# lune-v6-rev3_2.net
KiCad netlist of a schematic drawn in EasyEDA Pro
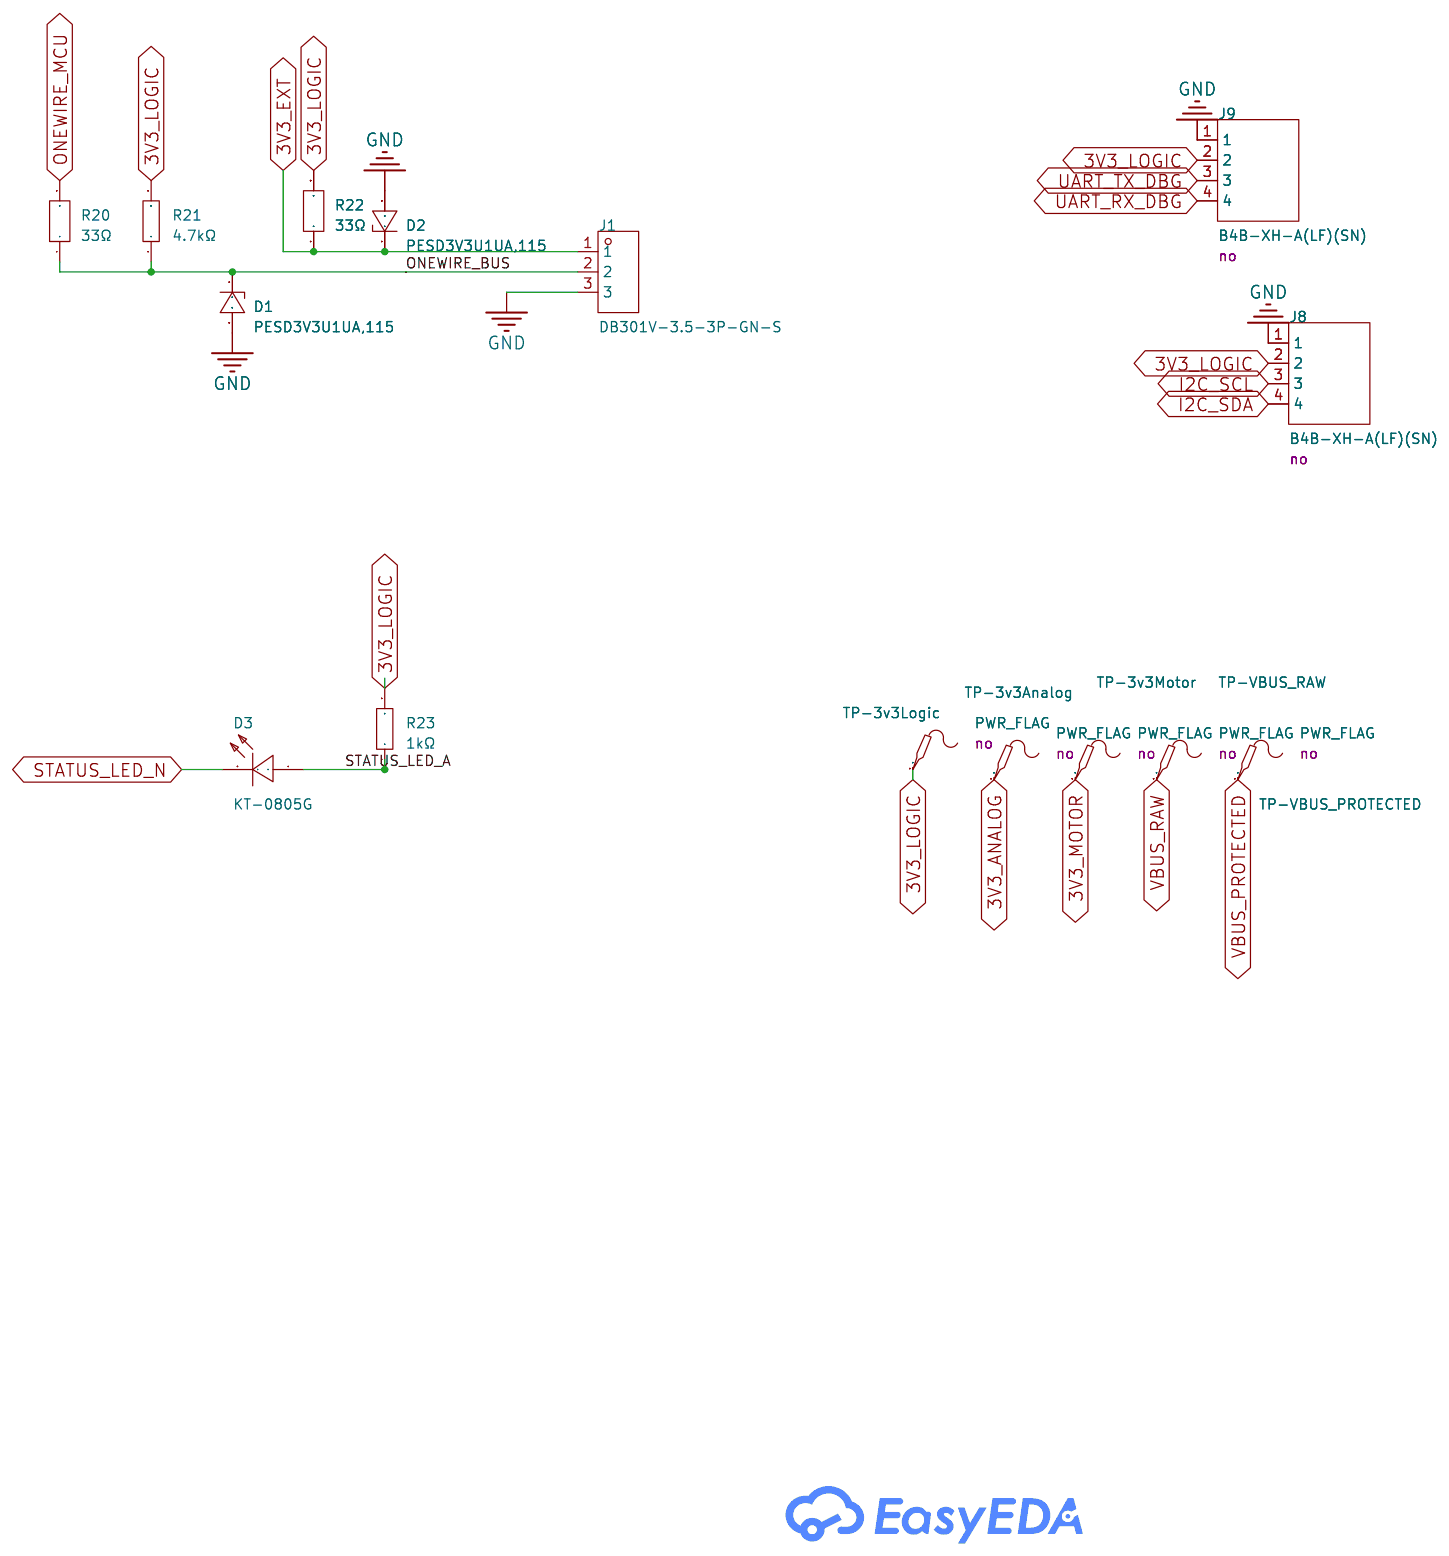
[diagram p0: Connectors]
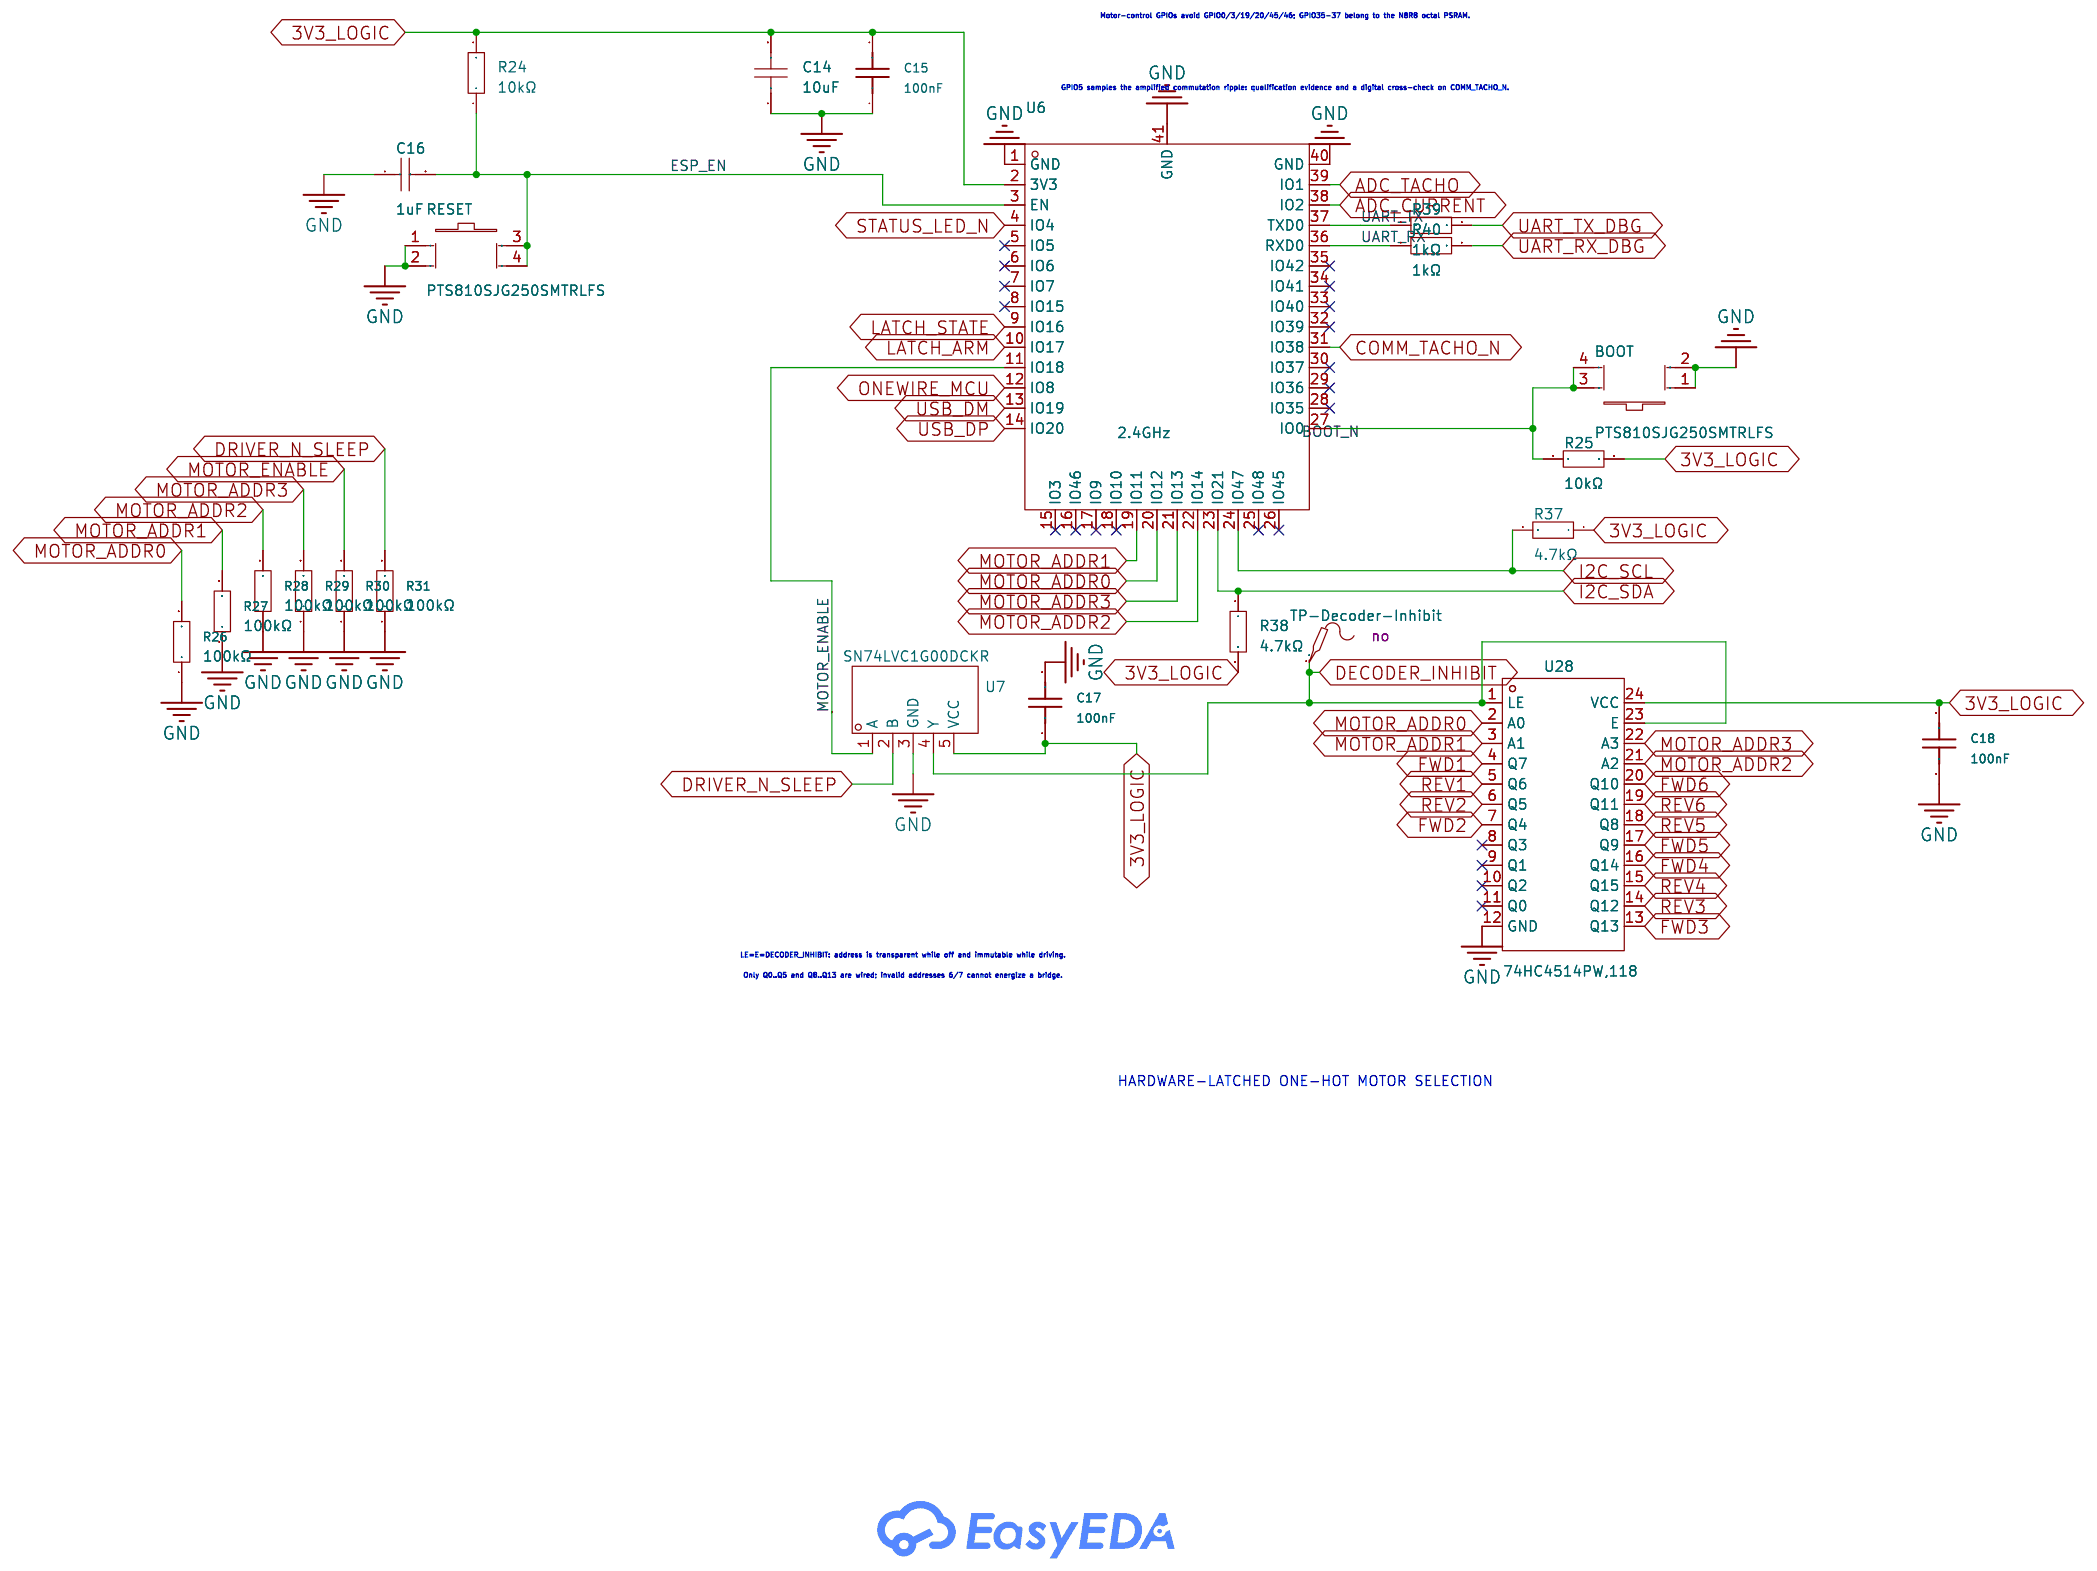
[diagram p1: Controller]
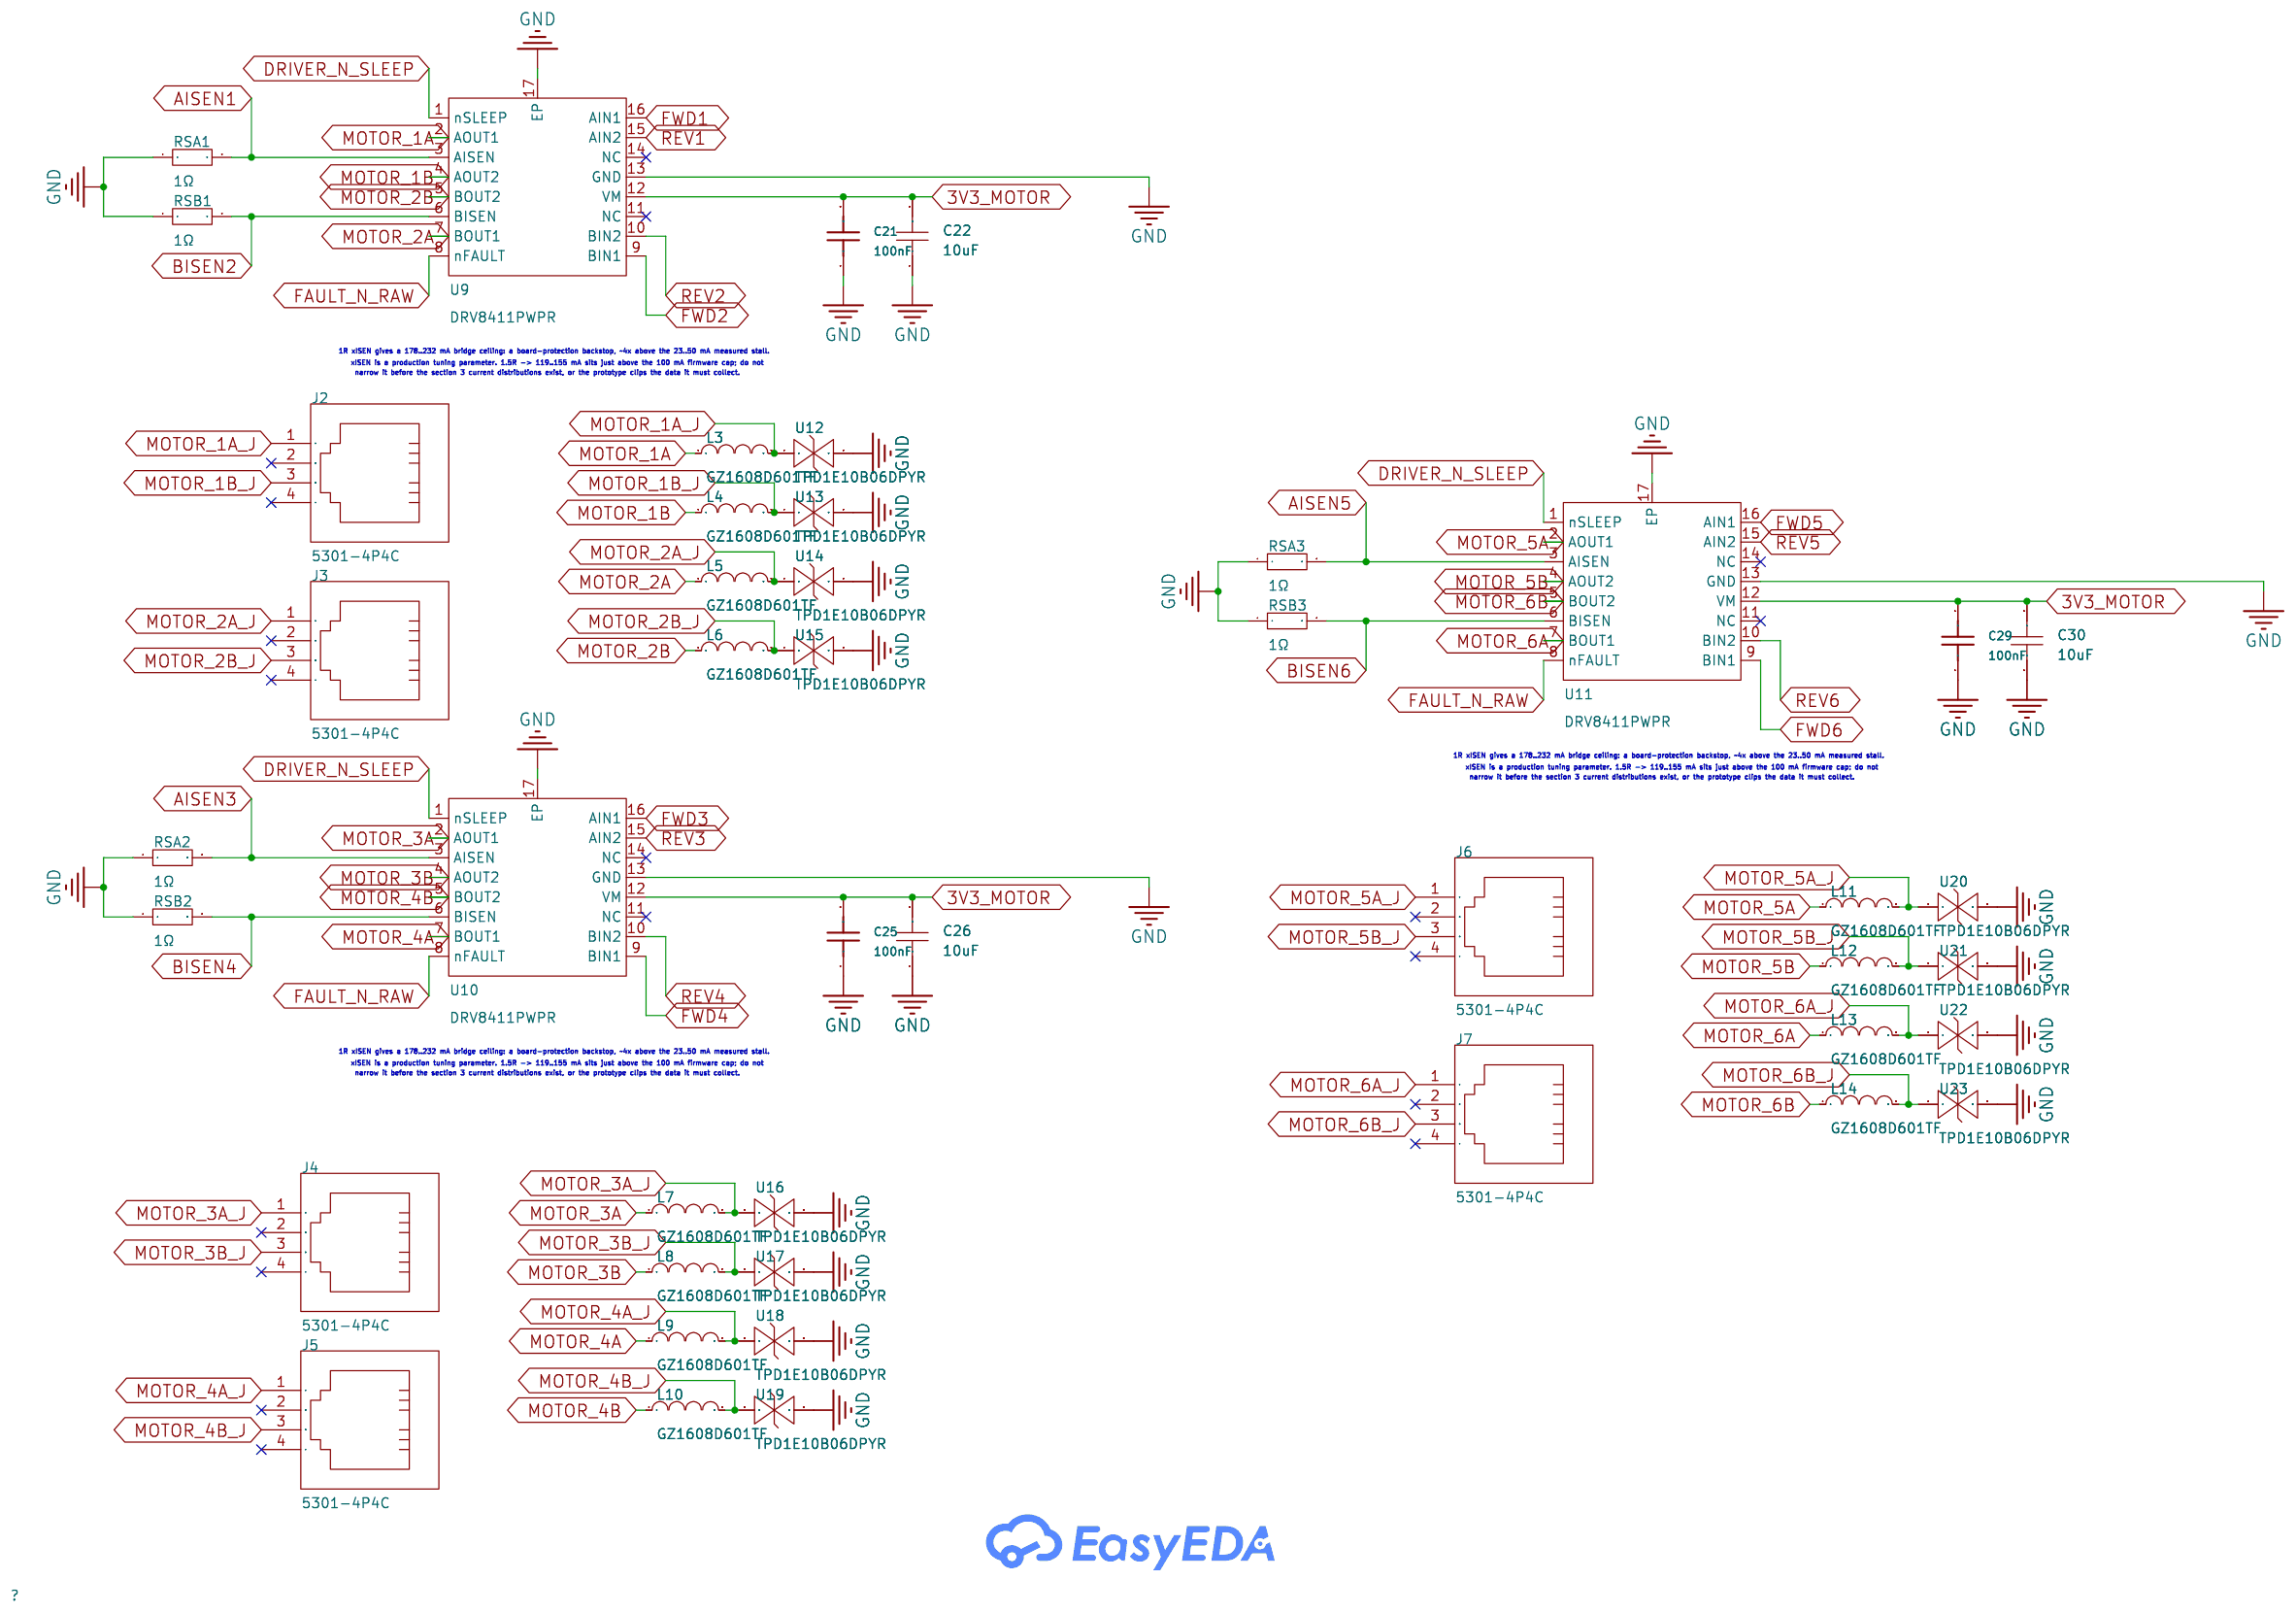
[diagram p2: Motors]
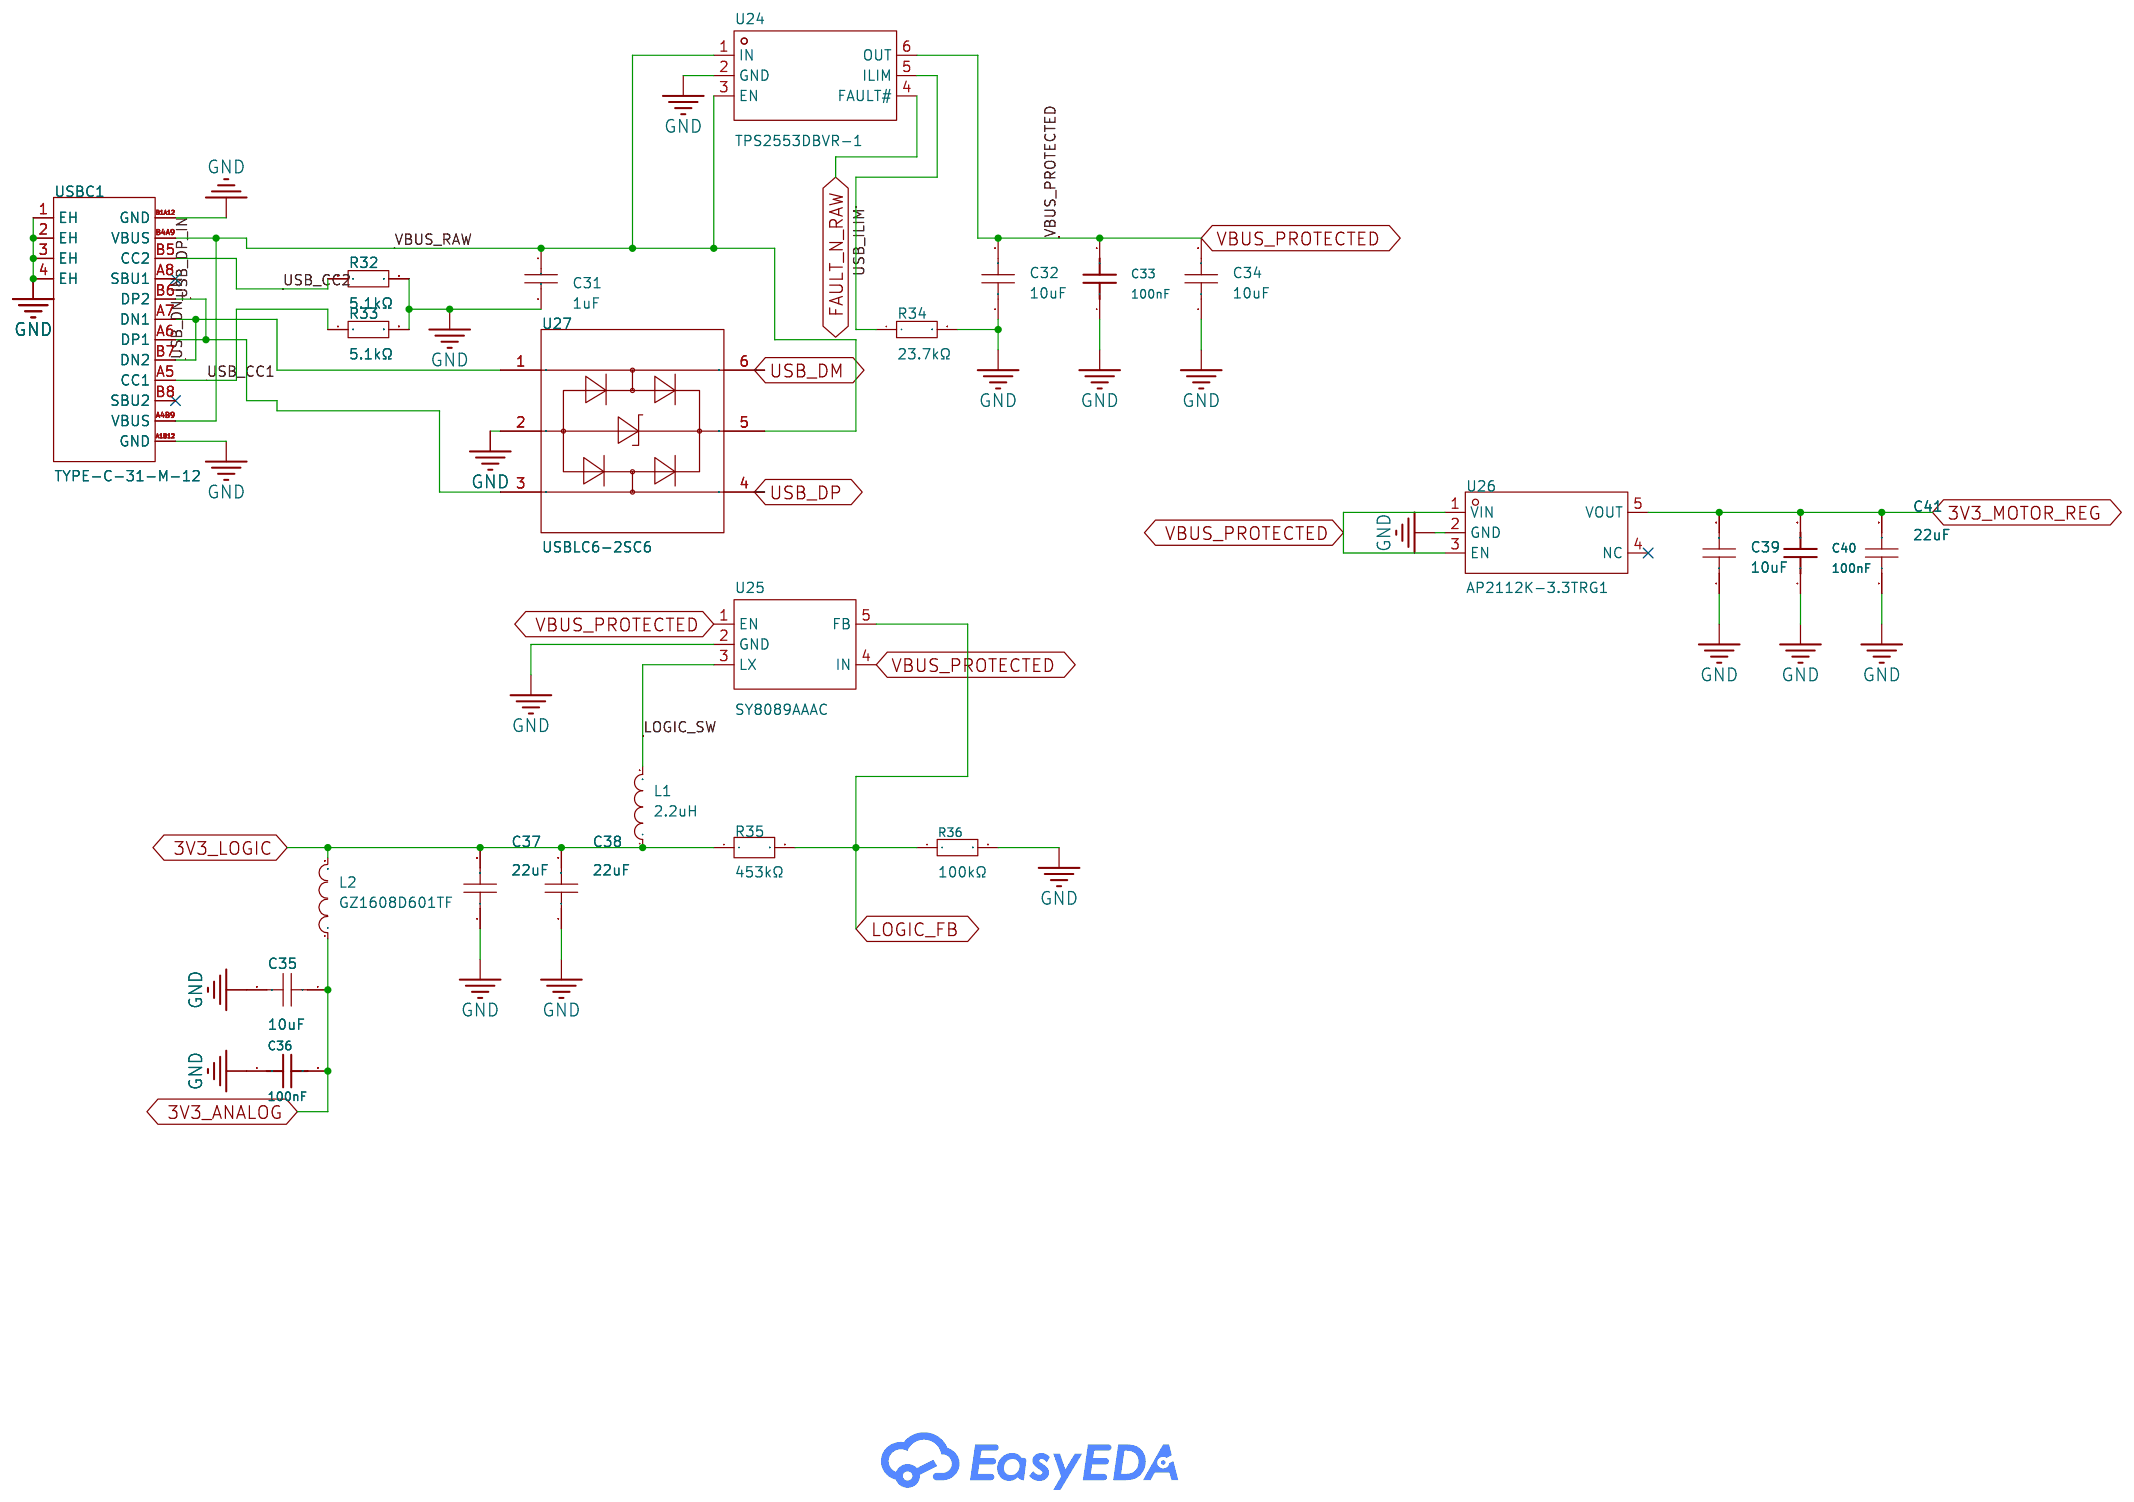
[diagram p3: Power]
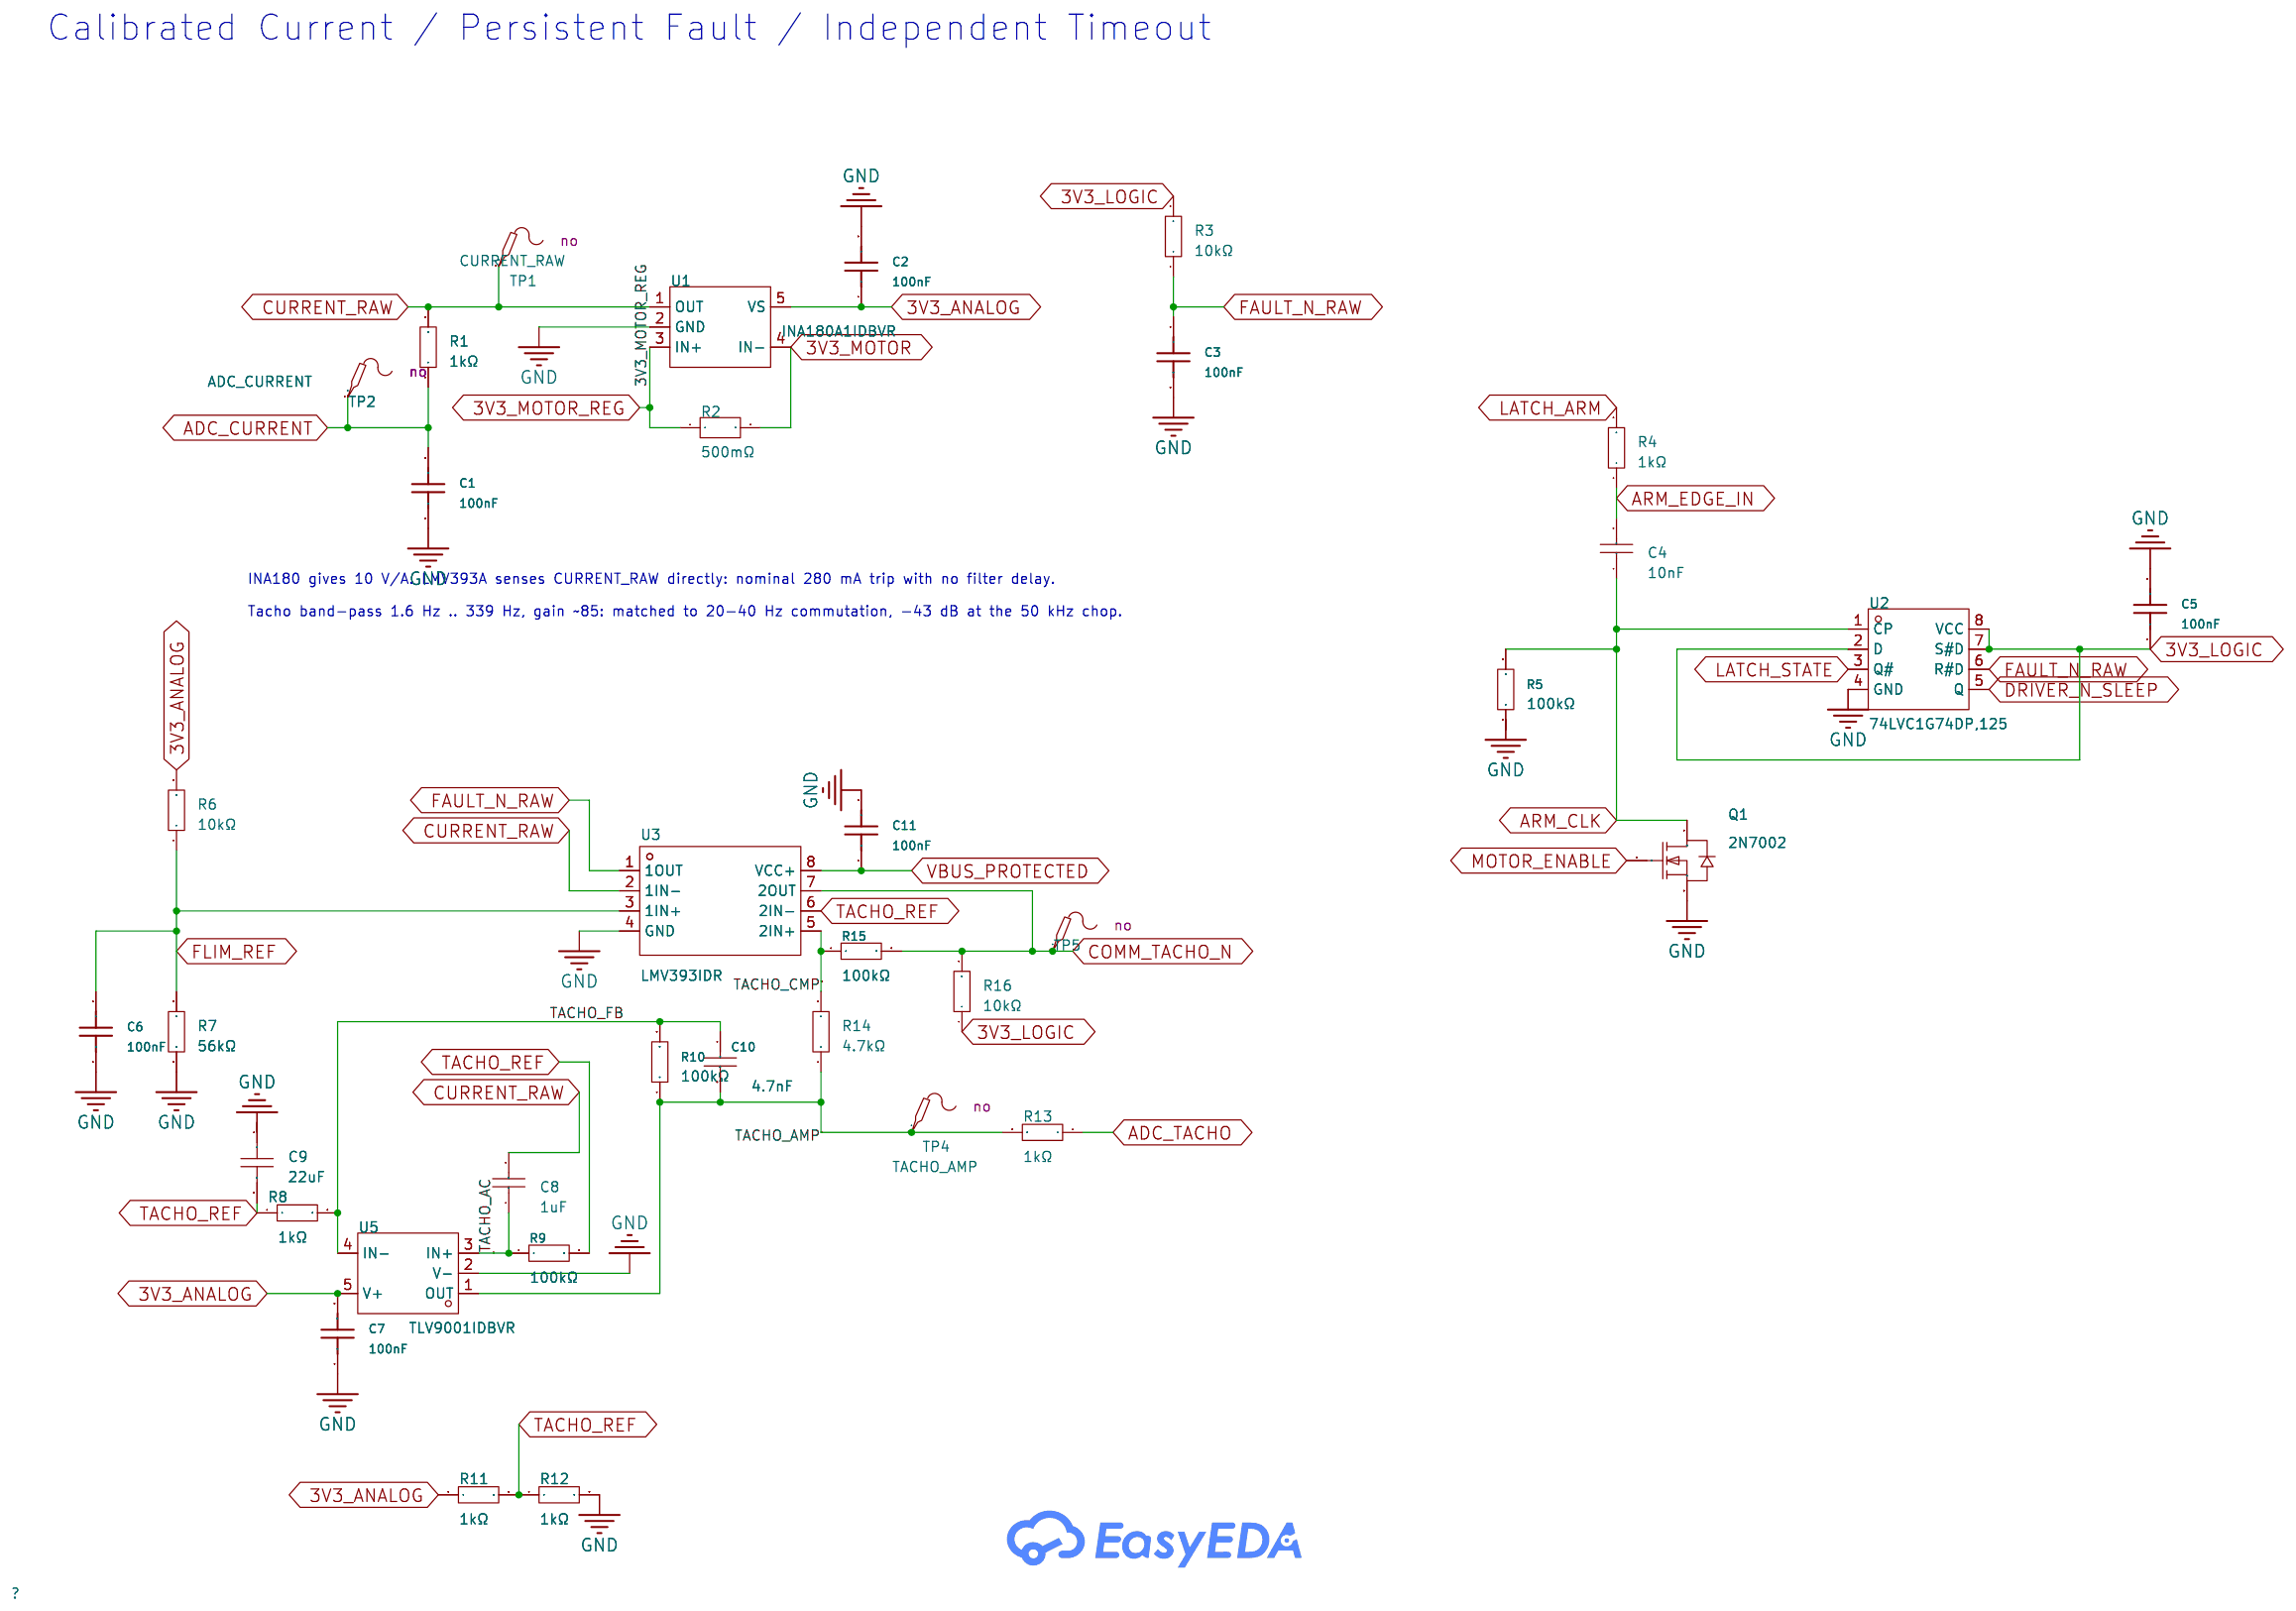
[diagram p4: Analog]

(export (version "E")
  (design (tool "Eeschema 10.0.6"))
  (components
    (comp (ref "D1")
      (value "PESD3V3U1UA,115")
      (footprint "easyedapro:SOD-323_L1.7-W1.3-LS2.5-RD")
      (fields (field (name "Manufacturer") "Nexperia(安世)"))
      (libsource (lib "easyedapro") (part "PESD3V3U1UA,115"))
    )
    (comp (ref "D2")
      (value "PESD3V3U1UA,115")
      (footprint "easyedapro:SOD-323_L1.7-W1.3-LS2.5-RD")
      (fields (field (name "Manufacturer") "Nexperia(安世)"))
      (libsource (lib "easyedapro") (part "PESD3V3U1UA,115"))
    )
    (comp (ref "D3")
      (value "KT-0805G")
      (footprint "easyedapro:LED0805-R-RD")
      (fields (field (name "Manufacturer") "KENTO"))
      (libsource (lib "easyedapro") (part "0805G (Green)"))
    )
    (comp (ref "J1")
      (value "DB301V-3.5-3P-GN-S")
      (footprint "easyedapro:CONN-TH_DB301V-3.5-3P-GN")
      (fields (field (name "Manufacturer") "DORABO(地博电气)"))
      (libsource (lib "easyedapro") (part "DB301V-3.5-3P-GN"))
    )
    (comp (ref "J8")
      (value "B4B-XH-A(LF)(SN)")
      (footprint "easyedapro:CONN-TH_B4B-XH-A-LF-SN")
      (fields (field (name "Manufacturer") "JST") (field (name "Add into BOM") "no"))
      (libsource (lib "easyedapro") (part "B4B-XH-A(LF)(SN)"))
    )
    (comp (ref "J9")
      (value "B4B-XH-A(LF)(SN)")
      (footprint "easyedapro:CONN-TH_B4B-XH-A-LF-SN")
      (fields (field (name "Manufacturer") "JST") (field (name "Add into BOM") "no"))
      (libsource (lib "easyedapro") (part "B4B-XH-A(LF)(SN)"))
    )
    (comp (ref "R20")
      (value "33Ω")
      (footprint "easyedapro:R0603")
      (fields
        (field (name "Manufacturer Part") "CRCW060333R0FKEA")
        (field (name "Manufacturer") "VISHAY(威世)")
      )
      (libsource (lib "easyedapro") (part "CRCW060333R0FKEA"))
    )
    (comp (ref "R21")
      (value "4.7kΩ")
      (footprint "easyedapro:R0603")
      (fields (field (name "Manufacturer Part") "RC0603FR-074K7L") (field (name "Manufacturer") "YAGEO(国巨)"))
      (libsource (lib "easyedapro") (part "RC0603FR-074K7L"))
    )
    (comp (ref "R22")
      (value "33Ω")
      (footprint "easyedapro:R0603")
      (fields
        (field (name "Manufacturer Part") "CRCW060333R0FKEA")
        (field (name "Manufacturer") "VISHAY(威世)")
      )
      (libsource (lib "easyedapro") (part "CRCW060333R0FKEA"))
    )
    (comp (ref "R23")
      (value "1kΩ")
      (footprint "easyedapro:R0603")
      (fields (field (name "Manufacturer Part") "RC0603FR-071KL") (field (name "Manufacturer") "YAGEO(国巨)"))
      (libsource (lib "easyedapro") (part "RC0603FR-071KL"))
    )
    (comp (ref "TP-3v3Analog")
      (value "PWR_FLAG")
      (footprint "easyedapro:Test-Point-0.5mm")
      (description "Test Point 测试点")
      (fields (field (name "Add into BOM") "no"))
      (libsource (lib "easyedapro") (part "Test-Point"))
    )
    (comp (ref "TP-3v3Logic")
      (value "PWR_FLAG")
      (footprint "easyedapro:Test-Point-0.5mm")
      (description "Test Point 测试点")
      (fields (field (name "Add into BOM") "no"))
      (libsource (lib "easyedapro") (part "Test-Point"))
    )
    (comp (ref "TP-3v3Motor")
      (value "PWR_FLAG")
      (footprint "easyedapro:Test-Point-0.5mm")
      (description "Test Point 测试点")
      (fields (field (name "Add into BOM") "no"))
      (libsource (lib "easyedapro") (part "Test-Point"))
    )
    (comp (ref "TP-VBUS_PROTECTED")
      (value "PWR_FLAG")
      (footprint "easyedapro:Test-Point-0.5mm")
      (description "Test Point 测试点")
      (fields (field (name "Add into BOM") "no"))
      (libsource (lib "easyedapro") (part "Test-Point"))
    )
    (comp (ref "TP-VBUS_RAW")
      (value "PWR_FLAG")
      (footprint "easyedapro:Test-Point-0.5mm")
      (description "Test Point 测试点")
      (fields (field (name "Add into BOM") "no"))
      (libsource (lib "easyedapro") (part "Test-Point"))
    )
    (comp (ref "BOOT")
      (value "PTS810SJG250SMTRLFS")
      (footprint "easyedapro:SW-SMD_4P_PTS810SJM250SMTRLFS")
      (fields (field (name "Manufacturer") "C&K"))
      (libsource (lib "easyedapro") (part "PTS810SJG250SMTRLFS"))
    )
    (comp (ref "C14")
      (value "10uF")
      (footprint "easyedapro:C0603")
      (description "Capacitance:10uF Tolerance:±10% Tolerance:±10% Voltage Rating:16V Temperature Coefficient:X5R")
      (fields
        (field (name "Manufacturer Part") "TCC0603X5R106K160CT")
        (field (name "Manufacturer") "CCTC(三环)")
      )
      (libsource (lib "easyedapro") (part "TCC0603X5R106K160CT"))
    )
    (comp (ref "C15")
      (value "100nF")
      (footprint "easyedapro:C0603")
      (description "Capacitance:100nF Tolerance:±10% Tolerance:±10% Voltage Rating:50V Temperature Coefficient:X7R")
      (fields
        (field (name "Manufacturer Part") "CC0603KRX7R9BB104")
        (field (name "Manufacturer") "YAGEO(国巨)")
      )
      (libsource (lib "easyedapro") (part "CC0603KRX7R9BB104"))
    )
    (comp (ref "C16")
      (value "1uF")
      (footprint "easyedapro:C0603")
      (description "Capacitance:1uF Tolerance:±10% Tolerance:±10% Voltage Rating:16V Temperature Coefficient:X7R")
      (fields (field (name "Manufacturer Part") "0603B105K160CT") (field (name "Manufacturer") "Walsin(华新科)"))
      (libsource (lib "easyedapro") (part "0603B105K160"))
    )
    (comp (ref "C17")
      (value "100nF")
      (footprint "easyedapro:C0603")
      (description "Capacitance:100nF Tolerance:±10% Tolerance:±10% Voltage Rating:50V Temperature Coefficient:X7R")
      (fields
        (field (name "Manufacturer Part") "CC0603KRX7R9BB104")
        (field (name "Manufacturer") "YAGEO(国巨)")
      )
      (libsource (lib "easyedapro") (part "CC0603KRX7R9BB104"))
    )
    (comp (ref "C18")
      (value "100nF")
      (footprint "easyedapro:C0603")
      (description "Capacitance:100nF Tolerance:±10% Tolerance:±10% Voltage Rating:50V Temperature Coefficient:X7R")
      (fields
        (field (name "Manufacturer Part") "CC0603KRX7R9BB104")
        (field (name "Manufacturer") "YAGEO(国巨)")
      )
      (libsource (lib "easyedapro") (part "CC0603KRX7R9BB104"))
    )
    (comp (ref "R24")
      (value "10kΩ")
      (footprint "easyedapro:R0603")
      (fields (field (name "Manufacturer Part") "RC0603FR-0710KL") (field (name "Manufacturer") "YAGEO(国巨)"))
      (libsource (lib "easyedapro") (part "RC0603FR-0710KL"))
    )
    (comp (ref "R25")
      (value "10kΩ")
      (footprint "easyedapro:R0603")
      (fields (field (name "Manufacturer Part") "RC0603FR-0710KL") (field (name "Manufacturer") "YAGEO(国巨)"))
      (libsource (lib "easyedapro") (part "RC0603FR-0710KL"))
    )
    (comp (ref "R26")
      (value "100kΩ")
      (footprint "easyedapro:R0603")
      (fields (field (name "Manufacturer Part") "RC0603FR-07100KL") (field (name "Manufacturer") "YAGEO(国巨)"))
      (libsource (lib "easyedapro") (part "RC0603FR-07100KL"))
    )
    (comp (ref "R27")
      (value "100kΩ")
      (footprint "easyedapro:R0603")
      (fields (field (name "Manufacturer Part") "RC0603FR-07100KL") (field (name "Manufacturer") "YAGEO(国巨)"))
      (libsource (lib "easyedapro") (part "RC0603FR-07100KL"))
    )
    (comp (ref "R28")
      (value "100kΩ")
      (footprint "easyedapro:R0603")
      (fields (field (name "Manufacturer Part") "RC0603FR-07100KL") (field (name "Manufacturer") "YAGEO(国巨)"))
      (libsource (lib "easyedapro") (part "RC0603FR-07100KL"))
    )
    (comp (ref "R29")
      (value "100kΩ")
      (footprint "easyedapro:R0603")
      (fields (field (name "Manufacturer Part") "RC0603FR-07100KL") (field (name "Manufacturer") "YAGEO(国巨)"))
      (libsource (lib "easyedapro") (part "RC0603FR-07100KL"))
    )
    (comp (ref "R30")
      (value "100kΩ")
      (footprint "easyedapro:R0603")
      (fields (field (name "Manufacturer Part") "RC0603FR-07100KL") (field (name "Manufacturer") "YAGEO(国巨)"))
      (libsource (lib "easyedapro") (part "RC0603FR-07100KL"))
    )
    (comp (ref "R31")
      (value "100kΩ")
      (footprint "easyedapro:R0603")
      (fields (field (name "Manufacturer Part") "RC0603FR-07100KL") (field (name "Manufacturer") "YAGEO(国巨)"))
      (libsource (lib "easyedapro") (part "RC0603FR-07100KL"))
    )
    (comp (ref "R37")
      (value "4.7kΩ")
      (footprint "easyedapro:R0603")
      (fields (field (name "Manufacturer Part") "RC0603FR-074K7L") (field (name "Manufacturer") "YAGEO(国巨)"))
      (libsource (lib "easyedapro") (part "RC0603FR-074K7L"))
    )
    (comp (ref "R38")
      (value "4.7kΩ")
      (footprint "easyedapro:R0603")
      (fields (field (name "Manufacturer Part") "RC0603FR-074K7L") (field (name "Manufacturer") "YAGEO(国巨)"))
      (libsource (lib "easyedapro") (part "RC0603FR-074K7L"))
    )
    (comp (ref "R39")
      (value "1kΩ")
      (footprint "easyedapro:R0603")
      (fields (field (name "Manufacturer Part") "RC0603FR-071KL") (field (name "Manufacturer") "YAGEO(国巨)"))
      (libsource (lib "easyedapro") (part "RC0603FR-071KL"))
    )
    (comp (ref "R40")
      (value "1kΩ")
      (footprint "easyedapro:R0603")
      (fields (field (name "Manufacturer Part") "RC0603FR-071KL") (field (name "Manufacturer") "YAGEO(国巨)"))
      (libsource (lib "easyedapro") (part "RC0603FR-071KL"))
    )
    (comp (ref "RESET")
      (value "PTS810SJG250SMTRLFS")
      (footprint "easyedapro:SW-SMD_4P_PTS810SJM250SMTRLFS")
      (fields (field (name "Manufacturer") "C&K"))
      (libsource (lib "easyedapro") (part "PTS810SJG250SMTRLFS"))
    )
    (comp (ref "TP-Decoder-Inhibit")
      (value "~")
      (footprint "easyedapro:Test-Point-0.5mm")
      (description "Test Point 测试点")
      (fields (field (name "Add into BOM") "no"))
      (libsource (lib "easyedapro") (part "Test-Point"))
    )
    (comp (ref "U6")
      (value "2.4GHz")
      (footprint "easyedapro:WIRELM-SMD_ESP32-S3-WROOM-1")
      (fields
        (field (name "Manufacturer Part") "ESP32-S3-WROOM-1-N8R8")
        (field (name "Manufacturer") "ESPRESSIF(乐鑫)")
      )
      (libsource (lib "easyedapro") (part "ESP32-S3-WROOM-1(N8R8)"))
    )
    (comp (ref "U7")
      (value "SN74LVC1G00DCKR")
      (footprint "easyedapro:SOT-353_L2.1-W1.3-P0.65-LS2.3-BR")
      (fields (field (name "Manufacturer") "TI(德州仪器)"))
      (libsource (lib "easyedapro") (part "SN74LVC1G00DCKR"))
    )
    (comp (ref "U28")
      (value "74HC4514PW,118")
      (footprint "easyedapro:TSSOP-24_L7.8-W4.4-P0.65-LS6.4-BL")
      (fields (field (name "Manufacturer") "Nexperia(安世)"))
      (libsource (lib "easyedapro") (part "74HC4514PW,118"))
    )
    (comp (ref "C21")
      (value "100nF")
      (footprint "easyedapro:C0603")
      (description "Capacitance:100nF Tolerance:±10% Tolerance:±10% Voltage Rating:50V Temperature Coefficient:X7R")
      (fields
        (field (name "Manufacturer Part") "CC0603KRX7R9BB104")
        (field (name "Manufacturer") "YAGEO(国巨)")
      )
      (libsource (lib "easyedapro") (part "CC0603KRX7R9BB104"))
    )
    (comp (ref "C22")
      (value "10uF")
      (footprint "easyedapro:C0603")
      (description "Capacitance:10uF Tolerance:±10% Tolerance:±10% Voltage Rating:16V Temperature Coefficient:X5R")
      (fields
        (field (name "Manufacturer Part") "TCC0603X5R106K160CT")
        (field (name "Manufacturer") "CCTC(三环)")
      )
      (libsource (lib "easyedapro") (part "TCC0603X5R106K160CT"))
    )
    (comp (ref "C25")
      (value "100nF")
      (footprint "easyedapro:C0603")
      (description "Capacitance:100nF Tolerance:±10% Tolerance:±10% Voltage Rating:50V Temperature Coefficient:X7R")
      (fields
        (field (name "Manufacturer Part") "CC0603KRX7R9BB104")
        (field (name "Manufacturer") "YAGEO(国巨)")
      )
      (libsource (lib "easyedapro") (part "CC0603KRX7R9BB104"))
    )
    (comp (ref "C26")
      (value "10uF")
      (footprint "easyedapro:C0603")
      (description "Capacitance:10uF Tolerance:±10% Tolerance:±10% Voltage Rating:16V Temperature Coefficient:X5R")
      (fields
        (field (name "Manufacturer Part") "TCC0603X5R106K160CT")
        (field (name "Manufacturer") "CCTC(三环)")
      )
      (libsource (lib "easyedapro") (part "TCC0603X5R106K160CT"))
    )
    (comp (ref "C29")
      (value "100nF")
      (footprint "easyedapro:C0603")
      (description "Capacitance:100nF Tolerance:±10% Tolerance:±10% Voltage Rating:50V Temperature Coefficient:X7R")
      (fields
        (field (name "Manufacturer Part") "CC0603KRX7R9BB104")
        (field (name "Manufacturer") "YAGEO(国巨)")
      )
      (libsource (lib "easyedapro") (part "CC0603KRX7R9BB104"))
    )
    (comp (ref "C30")
      (value "10uF")
      (footprint "easyedapro:C0603")
      (description "Capacitance:10uF Tolerance:±10% Tolerance:±10% Voltage Rating:16V Temperature Coefficient:X5R")
      (fields
        (field (name "Manufacturer Part") "TCC0603X5R106K160CT")
        (field (name "Manufacturer") "CCTC(三环)")
      )
      (libsource (lib "easyedapro") (part "TCC0603X5R106K160CT"))
    )
    (comp (ref "J2")
      (value "5301-4P4C")
      (footprint "easyedapro:RJ11-TH_RJ11-4P4C")
      (fields (field (name "Manufacturer") "EVERCOM(恒连)"))
      (libsource (lib "easyedapro") (part "5301-4P4C"))
    )
    (comp (ref "J3")
      (value "5301-4P4C")
      (footprint "easyedapro:RJ11-TH_RJ11-4P4C")
      (fields (field (name "Manufacturer") "EVERCOM(恒连)"))
      (libsource (lib "easyedapro") (part "5301-4P4C"))
    )
    (comp (ref "J4")
      (value "5301-4P4C")
      (footprint "easyedapro:RJ11-TH_RJ11-4P4C")
      (fields (field (name "Manufacturer") "EVERCOM(恒连)"))
      (libsource (lib "easyedapro") (part "5301-4P4C"))
    )
    (comp (ref "J5")
      (value "5301-4P4C")
      (footprint "easyedapro:RJ11-TH_RJ11-4P4C")
      (fields (field (name "Manufacturer") "EVERCOM(恒连)"))
      (libsource (lib "easyedapro") (part "5301-4P4C"))
    )
    (comp (ref "J6")
      (value "5301-4P4C")
      (footprint "easyedapro:RJ11-TH_RJ11-4P4C")
      (fields (field (name "Manufacturer") "EVERCOM(恒连)"))
      (libsource (lib "easyedapro") (part "5301-4P4C"))
    )
    (comp (ref "J7")
      (value "5301-4P4C")
      (footprint "easyedapro:RJ11-TH_RJ11-4P4C")
      (fields (field (name "Manufacturer") "EVERCOM(恒连)"))
      (libsource (lib "easyedapro") (part "5301-4P4C"))
    )
    (comp (ref "L3")
      (value "GZ1608D601TF")
      (footprint "easyedapro:L0603")
      (fields (field (name "Manufacturer") "Sunlord(顺络)"))
      (libsource (lib "easyedapro") (part "GZ1608D601TF"))
    )
    (comp (ref "L4")
      (value "GZ1608D601TF")
      (footprint "easyedapro:L0603")
      (fields (field (name "Manufacturer") "Sunlord(顺络)"))
      (libsource (lib "easyedapro") (part "GZ1608D601TF"))
    )
    (comp (ref "L5")
      (value "GZ1608D601TF")
      (footprint "easyedapro:L0603")
      (fields (field (name "Manufacturer") "Sunlord(顺络)"))
      (libsource (lib "easyedapro") (part "GZ1608D601TF"))
    )
    (comp (ref "L6")
      (value "GZ1608D601TF")
      (footprint "easyedapro:L0603")
      (fields (field (name "Manufacturer") "Sunlord(顺络)"))
      (libsource (lib "easyedapro") (part "GZ1608D601TF"))
    )
    (comp (ref "L7")
      (value "GZ1608D601TF")
      (footprint "easyedapro:L0603")
      (fields (field (name "Manufacturer") "Sunlord(顺络)"))
      (libsource (lib "easyedapro") (part "GZ1608D601TF"))
    )
    (comp (ref "L8")
      (value "GZ1608D601TF")
      (footprint "easyedapro:L0603")
      (fields (field (name "Manufacturer") "Sunlord(顺络)"))
      (libsource (lib "easyedapro") (part "GZ1608D601TF"))
    )
    (comp (ref "L9")
      (value "GZ1608D601TF")
      (footprint "easyedapro:L0603")
      (fields (field (name "Manufacturer") "Sunlord(顺络)"))
      (libsource (lib "easyedapro") (part "GZ1608D601TF"))
    )
    (comp (ref "L10")
      (value "GZ1608D601TF")
      (footprint "easyedapro:L0603")
      (fields (field (name "Manufacturer") "Sunlord(顺络)"))
      (libsource (lib "easyedapro") (part "GZ1608D601TF"))
    )
    (comp (ref "L11")
      (value "GZ1608D601TF")
      (footprint "easyedapro:L0603")
      (fields (field (name "Manufacturer") "Sunlord(顺络)"))
      (libsource (lib "easyedapro") (part "GZ1608D601TF"))
    )
    (comp (ref "L12")
      (value "GZ1608D601TF")
      (footprint "easyedapro:L0603")
      (fields (field (name "Manufacturer") "Sunlord(顺络)"))
      (libsource (lib "easyedapro") (part "GZ1608D601TF"))
    )
    (comp (ref "L13")
      (value "GZ1608D601TF")
      (footprint "easyedapro:L0603")
      (fields (field (name "Manufacturer") "Sunlord(顺络)"))
      (libsource (lib "easyedapro") (part "GZ1608D601TF"))
    )
    (comp (ref "L14")
      (value "GZ1608D601TF")
      (footprint "easyedapro:L0603")
      (fields (field (name "Manufacturer") "Sunlord(顺络)"))
      (libsource (lib "easyedapro") (part "GZ1608D601TF"))
    )
    (comp (ref "RSA1")
      (value "1Ω")
      (footprint "easyedapro:R0603")
      (fields (field (name "Manufacturer Part") "RC0603FR-071RL") (field (name "Manufacturer") "YAGEO(国巨)"))
      (libsource (lib "easyedapro") (part "RC0603FR-071RL"))
    )
    (comp (ref "RSA2")
      (value "1Ω")
      (footprint "easyedapro:R0603")
      (fields (field (name "Manufacturer Part") "RC0603FR-071RL") (field (name "Manufacturer") "YAGEO(国巨)"))
      (libsource (lib "easyedapro") (part "RC0603FR-071RL"))
    )
    (comp (ref "RSA3")
      (value "1Ω")
      (footprint "easyedapro:R0603")
      (fields (field (name "Manufacturer Part") "RC0603FR-071RL") (field (name "Manufacturer") "YAGEO(国巨)"))
      (libsource (lib "easyedapro") (part "RC0603FR-071RL"))
    )
    (comp (ref "RSB1")
      (value "1Ω")
      (footprint "easyedapro:R0603")
      (fields (field (name "Manufacturer Part") "RC0603FR-071RL") (field (name "Manufacturer") "YAGEO(国巨)"))
      (libsource (lib "easyedapro") (part "RC0603FR-071RL"))
    )
    (comp (ref "RSB2")
      (value "1Ω")
      (footprint "easyedapro:R0603")
      (fields (field (name "Manufacturer Part") "RC0603FR-071RL") (field (name "Manufacturer") "YAGEO(国巨)"))
      (libsource (lib "easyedapro") (part "RC0603FR-071RL"))
    )
    (comp (ref "RSB3")
      (value "1Ω")
      (footprint "easyedapro:R0603")
      (fields (field (name "Manufacturer Part") "RC0603FR-071RL") (field (name "Manufacturer") "YAGEO(国巨)"))
      (libsource (lib "easyedapro") (part "RC0603FR-071RL"))
    )
    (comp (ref "U9")
      (value "DRV8411PWPR")
      (footprint "easyedapro:HTSSOP-16_L5.0-W4.4-P0.65-LS6.4-TL-EP-1")
      (fields (field (name "Manufacturer") "TI(德州仪器)"))
      (libsource (lib "easyedapro") (part "DRV8411PWPR"))
    )
    (comp (ref "U10")
      (value "DRV8411PWPR")
      (footprint "easyedapro:HTSSOP-16_L5.0-W4.4-P0.65-LS6.4-TL-EP-1")
      (fields (field (name "Manufacturer") "TI(德州仪器)"))
      (libsource (lib "easyedapro") (part "DRV8411PWPR"))
    )
    (comp (ref "U11")
      (value "DRV8411PWPR")
      (footprint "easyedapro:HTSSOP-16_L5.0-W4.4-P0.65-LS6.4-TL-EP-1")
      (fields (field (name "Manufacturer") "TI(德州仪器)"))
      (libsource (lib "easyedapro") (part "DRV8411PWPR"))
    )
    (comp (ref "U12")
      (value "TPD1E10B06DPYR")
      (footprint "easyedapro:X1SON-2_L1.0-W0.6-P0.65-BI-1")
      (fields (field (name "Manufacturer") "TI(德州仪器)"))
      (libsource (lib "easyedapro") (part "TPD1E10B06DPYR"))
    )
    (comp (ref "U13")
      (value "TPD1E10B06DPYR")
      (footprint "easyedapro:X1SON-2_L1.0-W0.6-P0.65-BI-1")
      (fields (field (name "Manufacturer") "TI(德州仪器)"))
      (libsource (lib "easyedapro") (part "TPD1E10B06DPYR"))
    )
    (comp (ref "U14")
      (value "TPD1E10B06DPYR")
      (footprint "easyedapro:X1SON-2_L1.0-W0.6-P0.65-BI-1")
      (fields (field (name "Manufacturer") "TI(德州仪器)"))
      (libsource (lib "easyedapro") (part "TPD1E10B06DPYR"))
    )
    (comp (ref "U15")
      (value "TPD1E10B06DPYR")
      (footprint "easyedapro:X1SON-2_L1.0-W0.6-P0.65-BI-1")
      (fields (field (name "Manufacturer") "TI(德州仪器)"))
      (libsource (lib "easyedapro") (part "TPD1E10B06DPYR"))
    )
    (comp (ref "U16")
      (value "TPD1E10B06DPYR")
      (footprint "easyedapro:X1SON-2_L1.0-W0.6-P0.65-BI-1")
      (fields (field (name "Manufacturer") "TI(德州仪器)"))
      (libsource (lib "easyedapro") (part "TPD1E10B06DPYR"))
    )
    (comp (ref "U17")
      (value "TPD1E10B06DPYR")
      (footprint "easyedapro:X1SON-2_L1.0-W0.6-P0.65-BI-1")
      (fields (field (name "Manufacturer") "TI(德州仪器)"))
      (libsource (lib "easyedapro") (part "TPD1E10B06DPYR"))
    )
    (comp (ref "U18")
      (value "TPD1E10B06DPYR")
      (footprint "easyedapro:X1SON-2_L1.0-W0.6-P0.65-BI-1")
      (fields (field (name "Manufacturer") "TI(德州仪器)"))
      (libsource (lib "easyedapro") (part "TPD1E10B06DPYR"))
    )
    (comp (ref "U19")
      (value "TPD1E10B06DPYR")
      (footprint "easyedapro:X1SON-2_L1.0-W0.6-P0.65-BI-1")
      (fields (field (name "Manufacturer") "TI(德州仪器)"))
      (libsource (lib "easyedapro") (part "TPD1E10B06DPYR"))
    )
    (comp (ref "U20")
      (value "TPD1E10B06DPYR")
      (footprint "easyedapro:X1SON-2_L1.0-W0.6-P0.65-BI-1")
      (fields (field (name "Manufacturer") "TI(德州仪器)"))
      (libsource (lib "easyedapro") (part "TPD1E10B06DPYR"))
    )
    (comp (ref "U21")
      (value "TPD1E10B06DPYR")
      (footprint "easyedapro:X1SON-2_L1.0-W0.6-P0.65-BI-1")
      (fields (field (name "Manufacturer") "TI(德州仪器)"))
      (libsource (lib "easyedapro") (part "TPD1E10B06DPYR"))
    )
    (comp (ref "U22")
      (value "TPD1E10B06DPYR")
      (footprint "easyedapro:X1SON-2_L1.0-W0.6-P0.65-BI-1")
      (fields (field (name "Manufacturer") "TI(德州仪器)"))
      (libsource (lib "easyedapro") (part "TPD1E10B06DPYR"))
    )
    (comp (ref "U23")
      (value "TPD1E10B06DPYR")
      (footprint "easyedapro:X1SON-2_L1.0-W0.6-P0.65-BI-1")
      (fields (field (name "Manufacturer") "TI(德州仪器)"))
      (libsource (lib "easyedapro") (part "TPD1E10B06DPYR"))
    )
    (comp (ref "C31")
      (value "1uF")
      (footprint "easyedapro:C0603")
      (description "Capacitance:1uF Tolerance:±10% Tolerance:±10% Voltage Rating:16V Temperature Coefficient:X7R")
      (fields (field (name "Manufacturer Part") "0603B105K160CT") (field (name "Manufacturer") "Walsin(华新科)"))
      (libsource (lib "easyedapro") (part "0603B105K160"))
    )
    (comp (ref "C32")
      (value "10uF")
      (footprint "easyedapro:C0603")
      (description "Capacitance:10uF Tolerance:±10% Tolerance:±10% Voltage Rating:16V Temperature Coefficient:X5R")
      (fields
        (field (name "Manufacturer Part") "TCC0603X5R106K160CT")
        (field (name "Manufacturer") "CCTC(三环)")
      )
      (libsource (lib "easyedapro") (part "TCC0603X5R106K160CT"))
    )
    (comp (ref "C33")
      (value "100nF")
      (footprint "easyedapro:C0603")
      (description "Capacitance:100nF Tolerance:±10% Tolerance:±10% Voltage Rating:50V Temperature Coefficient:X7R")
      (fields
        (field (name "Manufacturer Part") "CC0603KRX7R9BB104")
        (field (name "Manufacturer") "YAGEO(国巨)")
      )
      (libsource (lib "easyedapro") (part "CC0603KRX7R9BB104"))
    )
    (comp (ref "C34")
      (value "10uF")
      (footprint "easyedapro:C0603")
      (description "Capacitance:10uF Tolerance:±10% Tolerance:±10% Voltage Rating:16V Temperature Coefficient:X5R")
      (fields
        (field (name "Manufacturer Part") "TCC0603X5R106K160CT")
        (field (name "Manufacturer") "CCTC(三环)")
      )
      (libsource (lib "easyedapro") (part "TCC0603X5R106K160CT"))
    )
    (comp (ref "C35")
      (value "10uF")
      (footprint "easyedapro:C0603")
      (description "Capacitance:10uF Tolerance:±10% Tolerance:±10% Voltage Rating:16V Temperature Coefficient:X5R")
      (fields
        (field (name "Manufacturer Part") "TCC0603X5R106K160CT")
        (field (name "Manufacturer") "CCTC(三环)")
      )
      (libsource (lib "easyedapro") (part "TCC0603X5R106K160CT"))
    )
    (comp (ref "C36")
      (value "100nF")
      (footprint "easyedapro:C0603")
      (description "Capacitance:100nF Tolerance:±10% Tolerance:±10% Voltage Rating:50V Temperature Coefficient:X7R")
      (fields
        (field (name "Manufacturer Part") "CC0603KRX7R9BB104")
        (field (name "Manufacturer") "YAGEO(国巨)")
      )
      (libsource (lib "easyedapro") (part "CC0603KRX7R9BB104"))
    )
    (comp (ref "C37")
      (value "22uF")
      (footprint "easyedapro:C0805")
      (description "Capacitance:22uF Tolerance:±10% Tolerance:±10% Voltage Rating:6.3V Temperature Coefficient:X5R")
      (fields
        (field (name "Manufacturer Part") "TCC0805X5R226K6R3FT")
        (field (name "Manufacturer") "CCTC(三环)")
      )
      (libsource (lib "easyedapro") (part "TCC0805X5R226K6R3FT"))
    )
    (comp (ref "C38")
      (value "22uF")
      (footprint "easyedapro:C0805")
      (description "Capacitance:22uF Tolerance:±10% Tolerance:±10% Voltage Rating:6.3V Temperature Coefficient:X5R")
      (fields
        (field (name "Manufacturer Part") "TCC0805X5R226K6R3FT")
        (field (name "Manufacturer") "CCTC(三环)")
      )
      (libsource (lib "easyedapro") (part "TCC0805X5R226K6R3FT"))
    )
    (comp (ref "C39")
      (value "10uF")
      (footprint "easyedapro:C0603")
      (description "Capacitance:10uF Tolerance:±10% Tolerance:±10% Voltage Rating:16V Temperature Coefficient:X5R")
      (fields
        (field (name "Manufacturer Part") "TCC0603X5R106K160CT")
        (field (name "Manufacturer") "CCTC(三环)")
      )
      (libsource (lib "easyedapro") (part "TCC0603X5R106K160CT"))
    )
    (comp (ref "C40")
      (value "100nF")
      (footprint "easyedapro:C0603")
      (description "Capacitance:100nF Tolerance:±10% Tolerance:±10% Voltage Rating:50V Temperature Coefficient:X7R")
      (fields
        (field (name "Manufacturer Part") "CC0603KRX7R9BB104")
        (field (name "Manufacturer") "YAGEO(国巨)")
      )
      (libsource (lib "easyedapro") (part "CC0603KRX7R9BB104"))
    )
    (comp (ref "C41")
      (value "22uF")
      (footprint "easyedapro:C0805")
      (description "Capacitance:22uF Tolerance:±10% Tolerance:±10% Voltage Rating:6.3V Temperature Coefficient:X5R")
      (fields
        (field (name "Manufacturer Part") "TCC0805X5R226K6R3FT")
        (field (name "Manufacturer") "CCTC(三环)")
      )
      (libsource (lib "easyedapro") (part "TCC0805X5R226K6R3FT"))
    )
    (comp (ref "L1")
      (value "2.2uH")
      (footprint "easyedapro:IND-SMD_L4.0-W4.0")
      (fields (field (name "Manufacturer Part") "SPH4018H2R2MT") (field (name "Manufacturer") "Sunlord(顺络)"))
      (libsource (lib "easyedapro") (part "SPH4018H2R2MT"))
    )
    (comp (ref "L2")
      (value "GZ1608D601TF")
      (footprint "easyedapro:L0603")
      (fields (field (name "Manufacturer") "Sunlord(顺络)"))
      (libsource (lib "easyedapro") (part "GZ1608D601TF"))
    )
    (comp (ref "R32")
      (value "5.1kΩ")
      (footprint "easyedapro:R0603")
      (fields
        (field (name "Manufacturer Part") "0603WAF5101T5E")
        (field (name "Manufacturer") "UNI-ROYAL(厚声)")
      )
      (libsource (lib "easyedapro") (part "0603WAF5101T5E"))
    )
    (comp (ref "R33")
      (value "5.1kΩ")
      (footprint "easyedapro:R0603")
      (fields
        (field (name "Manufacturer Part") "0603WAF5101T5E")
        (field (name "Manufacturer") "UNI-ROYAL(厚声)")
      )
      (libsource (lib "easyedapro") (part "0603WAF5101T5E"))
    )
    (comp (ref "R34")
      (value "23.7kΩ")
      (footprint "easyedapro:R0603")
      (fields
        (field (name "Manufacturer Part") "0603WAF2372T5E")
        (field (name "Manufacturer") "UNI-ROYAL(厚声)")
      )
      (libsource (lib "easyedapro") (part "0603WAF2372T5E"))
    )
    (comp (ref "R35")
      (value "453kΩ")
      (footprint "easyedapro:R0603")
      (fields (field (name "Manufacturer Part") "RC0603FR-07453KL") (field (name "Manufacturer") "YAGEO(国巨)"))
      (libsource (lib "easyedapro") (part "RC0603FR-07453KL"))
    )
    (comp (ref "R36")
      (value "100kΩ")
      (footprint "easyedapro:R0603")
      (fields (field (name "Manufacturer Part") "RC0603FR-07100KL") (field (name "Manufacturer") "YAGEO(国巨)"))
      (libsource (lib "easyedapro") (part "RC0603FR-07100KL"))
    )
    (comp (ref "U24")
      (value "TPS2553DBVR-1")
      (footprint "easyedapro:SOT-23-6_L2.9-W1.6-P0.95-LS2.8-BL")
      (fields (field (name "Manufacturer") "TI(德州仪器)"))
      (libsource (lib "easyedapro") (part "TPS2553DBVR-1"))
    )
    (comp (ref "U25")
      (value "SY8089AAAC")
      (footprint "easyedapro:SOT-23-5_L3.0-W1.7-P0.95-LS2.8-BR")
      (fields (field (name "Manufacturer") "Silergy(矽力杰)"))
      (libsource (lib "easyedapro") (part "SY8089AAAC"))
    )
    (comp (ref "U26")
      (value "AP2112K-3.3TRG1")
      (footprint "easyedapro:SOT-25-5_L2.9-W1.6-P0.95-LS2.8-BL")
      (fields (field (name "Manufacturer") "DIODES(美台)"))
      (libsource (lib "easyedapro") (part "AP2112K-3.3TRG1"))
    )
    (comp (ref "U27")
      (value "USBLC6-2SC6")
      (footprint "easyedapro:SOT-23-6_L2.9-W1.6-P0.95-LS2.8-BL")
      (fields (field (name "Manufacturer") "ST(意法半导体)"))
      (libsource (lib "easyedapro") (part "USBLC6-2SC6"))
    )
    (comp (ref "USBC1")
      (value "TYPE-C-31-M-12")
      (footprint "easyedapro:USB-C_SMD-TYPE-C-31-M-12_1")
      (fields (field (name "Manufacturer") "韩国韩荣"))
      (libsource (lib "easyedapro") (part "TYPE-C-31-M-12"))
    )
    (comp (ref "C1")
      (value "100nF")
      (footprint "easyedapro:C0603")
      (description "Capacitance:100nF Tolerance:±10% Tolerance:±10% Voltage Rating:50V Temperature Coefficient:X7R")
      (fields
        (field (name "Manufacturer Part") "CC0603KRX7R9BB104")
        (field (name "Manufacturer") "YAGEO(国巨)")
      )
      (libsource (lib "easyedapro") (part "CC0603KRX7R9BB104"))
    )
    (comp (ref "C2")
      (value "100nF")
      (footprint "easyedapro:C0603")
      (description "Capacitance:100nF Tolerance:±10% Tolerance:±10% Voltage Rating:50V Temperature Coefficient:X7R")
      (fields
        (field (name "Manufacturer Part") "CC0603KRX7R9BB104")
        (field (name "Manufacturer") "YAGEO(国巨)")
      )
      (libsource (lib "easyedapro") (part "CC0603KRX7R9BB104"))
    )
    (comp (ref "C3")
      (value "100nF")
      (footprint "easyedapro:C0603")
      (description "Capacitance:100nF Tolerance:±10% Tolerance:±10% Voltage Rating:50V Temperature Coefficient:X7R")
      (fields
        (field (name "Manufacturer Part") "CC0603KRX7R9BB104")
        (field (name "Manufacturer") "YAGEO(国巨)")
      )
      (libsource (lib "easyedapro") (part "CC0603KRX7R9BB104"))
    )
    (comp (ref "C4")
      (value "10nF")
      (footprint "easyedapro:C0603")
      (description "Capacitance:10nF Tolerance:±10% Tolerance:±10% Voltage Rating:50V Temperature Coefficient:X7R")
      (fields
        (field (name "Manufacturer Part") "CL10B103KB8NNNC")
        (field (name "Manufacturer") "SAMSUNG(三星)")
      )
      (libsource (lib "easyedapro") (part "CL10B103KB8NNNC"))
    )
    (comp (ref "C5")
      (value "100nF")
      (footprint "easyedapro:C0603")
      (description "Capacitance:100nF Tolerance:±10% Tolerance:±10% Voltage Rating:50V Temperature Coefficient:X7R")
      (fields
        (field (name "Manufacturer Part") "CC0603KRX7R9BB104")
        (field (name "Manufacturer") "YAGEO(国巨)")
      )
      (libsource (lib "easyedapro") (part "CC0603KRX7R9BB104"))
    )
    (comp (ref "C6")
      (value "100nF")
      (footprint "easyedapro:C0603")
      (description "Capacitance:100nF Tolerance:±10% Tolerance:±10% Voltage Rating:50V Temperature Coefficient:X7R")
      (fields
        (field (name "Manufacturer Part") "CC0603KRX7R9BB104")
        (field (name "Manufacturer") "YAGEO(国巨)")
      )
      (libsource (lib "easyedapro") (part "CC0603KRX7R9BB104"))
    )
    (comp (ref "C7")
      (value "100nF")
      (footprint "easyedapro:C0603")
      (description "Capacitance:100nF Tolerance:±10% Tolerance:±10% Voltage Rating:50V Temperature Coefficient:X7R")
      (fields
        (field (name "Manufacturer Part") "CC0603KRX7R9BB104")
        (field (name "Manufacturer") "YAGEO(国巨)")
      )
      (libsource (lib "easyedapro") (part "CC0603KRX7R9BB104"))
    )
    (comp (ref "C8")
      (value "1uF")
      (footprint "easyedapro:C0603")
      (description "Capacitance:1uF Tolerance:±10% Tolerance:±10% Voltage Rating:16V Temperature Coefficient:X7R")
      (fields (field (name "Manufacturer Part") "0603B105K160CT") (field (name "Manufacturer") "Walsin(华新科)"))
      (libsource (lib "easyedapro") (part "0603B105K160"))
    )
    (comp (ref "C9")
      (value "22uF")
      (footprint "easyedapro:C0805")
      (description "Capacitance:22uF Tolerance:±10% Tolerance:±10% Voltage Rating:6.3V Temperature Coefficient:X5R")
      (fields
        (field (name "Manufacturer Part") "TCC0805X5R226K6R3FT")
        (field (name "Manufacturer") "CCTC(三环)")
      )
      (libsource (lib "easyedapro") (part "TCC0805X5R226K6R3FT"))
    )
    (comp (ref "C10")
      (value "4.7nF")
      (footprint "easyedapro:C0603")
      (description "Capacitance:4.7nF Tolerance:±10% Tolerance:±10% Voltage Rating:50V Temperature Coefficient:X7R")
      (fields
        (field (name "Manufacturer Part") "CC0603KRX7R9BB472")
        (field (name "Manufacturer") "YAGEO(国巨)")
      )
      (libsource (lib "easyedapro") (part "CC0603KRX7R9BB472"))
    )
    (comp (ref "C11")
      (value "100nF")
      (footprint "easyedapro:C0603")
      (description "Capacitance:100nF Tolerance:±10% Tolerance:±10% Voltage Rating:50V Temperature Coefficient:X7R")
      (fields
        (field (name "Manufacturer Part") "CC0603KRX7R9BB104")
        (field (name "Manufacturer") "YAGEO(国巨)")
      )
      (libsource (lib "easyedapro") (part "CC0603KRX7R9BB104"))
    )
    (comp (ref "Q1")
      (value "2N7002")
      (footprint "easyedapro:SOT-23-3_L2.9-W1.3-P1.90-LS2.4-BR")
      (fields (field (name "Manufacturer") "CJ(江苏长电/长晶)"))
      (libsource (lib "easyedapro") (part "2N7002"))
    )
    (comp (ref "R1")
      (value "1kΩ")
      (footprint "easyedapro:R0603")
      (fields (field (name "Manufacturer Part") "RC0603FR-071KL") (field (name "Manufacturer") "YAGEO(国巨)"))
      (libsource (lib "easyedapro") (part "RC0603FR-071KL"))
    )
    (comp (ref "R2")
      (value "500mΩ")
      (footprint "easyedapro:R1206")
      (fields
        (field (name "Manufacturer Part") "HoYH1206-1W-500mR-1%")
        (field (name "Manufacturer") "Milliohm(毫欧)")
      )
      (libsource (lib "easyedapro") (part "HOYH1206-1W-500MR-1%"))
    )
    (comp (ref "R3")
      (value "10kΩ")
      (footprint "easyedapro:R0603")
      (fields (field (name "Manufacturer Part") "RC0603FR-0710KL") (field (name "Manufacturer") "YAGEO(国巨)"))
      (libsource (lib "easyedapro") (part "RC0603FR-0710KL"))
    )
    (comp (ref "R4")
      (value "1kΩ")
      (footprint "easyedapro:R0603")
      (fields (field (name "Manufacturer Part") "RC0603FR-071KL") (field (name "Manufacturer") "YAGEO(国巨)"))
      (libsource (lib "easyedapro") (part "RC0603FR-071KL"))
    )
    (comp (ref "R5")
      (value "100kΩ")
      (footprint "easyedapro:R0603")
      (fields (field (name "Manufacturer Part") "RC0603FR-07100KL") (field (name "Manufacturer") "YAGEO(国巨)"))
      (libsource (lib "easyedapro") (part "RC0603FR-07100KL"))
    )
    (comp (ref "R6")
      (value "10kΩ")
      (footprint "easyedapro:R0603")
      (fields (field (name "Manufacturer Part") "RC0603FR-0710KL") (field (name "Manufacturer") "YAGEO(国巨)"))
      (libsource (lib "easyedapro") (part "RC0603FR-0710KL"))
    )
    (comp (ref "R7")
      (value "56kΩ")
      (footprint "easyedapro:R0603")
      (fields (field (name "Manufacturer Part") "RC0603FR-0756KL") (field (name "Manufacturer") "YAGEO(国巨)"))
      (libsource (lib "easyedapro") (part "RC0603FR-0756KL"))
    )
    (comp (ref "R8")
      (value "1kΩ")
      (footprint "easyedapro:R0603")
      (fields (field (name "Manufacturer Part") "RC0603FR-071KL") (field (name "Manufacturer") "YAGEO(国巨)"))
      (libsource (lib "easyedapro") (part "RC0603FR-071KL"))
    )
    (comp (ref "R9")
      (value "100kΩ")
      (footprint "easyedapro:R0603")
      (fields (field (name "Manufacturer Part") "RC0603FR-07100KL") (field (name "Manufacturer") "YAGEO(国巨)"))
      (libsource (lib "easyedapro") (part "RC0603FR-07100KL"))
    )
    (comp (ref "R10")
      (value "100kΩ")
      (footprint "easyedapro:R0603")
      (fields (field (name "Manufacturer Part") "RC0603FR-07100KL") (field (name "Manufacturer") "YAGEO(国巨)"))
      (libsource (lib "easyedapro") (part "RC0603FR-07100KL"))
    )
    (comp (ref "R11")
      (value "1kΩ")
      (footprint "easyedapro:R0603")
      (fields (field (name "Manufacturer Part") "RC0603FR-071KL") (field (name "Manufacturer") "YAGEO(国巨)"))
      (libsource (lib "easyedapro") (part "RC0603FR-071KL"))
    )
    (comp (ref "R12")
      (value "1kΩ")
      (footprint "easyedapro:R0603")
      (fields (field (name "Manufacturer Part") "RC0603FR-071KL") (field (name "Manufacturer") "YAGEO(国巨)"))
      (libsource (lib "easyedapro") (part "RC0603FR-071KL"))
    )
    (comp (ref "R13")
      (value "1kΩ")
      (footprint "easyedapro:R0603")
      (fields (field (name "Manufacturer Part") "RC0603FR-071KL") (field (name "Manufacturer") "YAGEO(国巨)"))
      (libsource (lib "easyedapro") (part "RC0603FR-071KL"))
    )
    (comp (ref "R14")
      (value "4.7kΩ")
      (footprint "easyedapro:R0603")
      (fields (field (name "Manufacturer Part") "RC0603FR-074K7L") (field (name "Manufacturer") "YAGEO(国巨)"))
      (libsource (lib "easyedapro") (part "RC0603FR-074K7L"))
    )
    (comp (ref "R15")
      (value "100kΩ")
      (footprint "easyedapro:R0603")
      (fields (field (name "Manufacturer Part") "RC0603FR-07100KL") (field (name "Manufacturer") "YAGEO(国巨)"))
      (libsource (lib "easyedapro") (part "RC0603FR-07100KL"))
    )
    (comp (ref "R16")
      (value "10kΩ")
      (footprint "easyedapro:R0603")
      (fields (field (name "Manufacturer Part") "RC0603FR-0710KL") (field (name "Manufacturer") "YAGEO(国巨)"))
      (libsource (lib "easyedapro") (part "RC0603FR-0710KL"))
    )
    (comp (ref "TP1")
      (value "CURRENT_RAW")
      (footprint "easyedapro:Test-Point-0.5mm")
      (description "Test Point 测试点")
      (fields (field (name "Add into BOM") "no"))
      (libsource (lib "easyedapro") (part "Test-Point"))
    )
    (comp (ref "TP2")
      (value "ADC_CURRENT")
      (footprint "easyedapro:Test-Point-0.5mm")
      (description "Test Point 测试点")
      (fields (field (name "Add into BOM") "no"))
      (libsource (lib "easyedapro") (part "Test-Point"))
    )
    (comp (ref "TP4")
      (value "TACHO_AMP")
      (footprint "easyedapro:Test-Point-0.5mm")
      (description "Test Point 测试点")
      (fields (field (name "Add into BOM") "no"))
      (libsource (lib "easyedapro") (part "Test-Point"))
    )
    (comp (ref "TP5")
      (value "~")
      (footprint "easyedapro:Test-Point-0.5mm")
      (description "Test Point 测试点")
      (fields (field (name "Add into BOM") "no"))
      (libsource (lib "easyedapro") (part "Test-Point"))
    )
    (comp (ref "U1")
      (value "INA180A1IDBVR")
      (footprint "easyedapro:SOT-23-5_L3.0-W1.7-P0.95-LS2.8-BR")
      (fields (field (name "Manufacturer") "TI(德州仪器)"))
      (libsource (lib "easyedapro") (part "INA180A1IDBVR"))
    )
    (comp (ref "U2")
      (value "74LVC1G74DP,125")
      (footprint "easyedapro:TSSOP-8_L3.0-W3.0-P0.65-LS4.0-BL")
      (fields (field (name "Manufacturer") "Nexperia(安世)"))
      (libsource (lib "easyedapro") (part "74LVC1G74DP,125"))
    )
    (comp (ref "U3")
      (value "LMV393IDR")
      (footprint "easyedapro:SOIC-8_L5.0-W4.0-P1.27-LS6.0-BL")
      (fields (field (name "Manufacturer") "TI(德州仪器)"))
      (libsource (lib "easyedapro") (part "LMV393IDR"))
    )
    (comp (ref "U5")
      (value "TLV9001IDBVR")
      (footprint "easyedapro:SOT-23-5_L3.0-W1.7-P0.95-LS2.8-BR")
      (fields (field (name "Manufacturer") "TI(德州仪器)"))
      (libsource (lib "easyedapro") (part "TLV9001IDBVR"))
    )
  )
  (nets
    (net (code "1") (name "3V3_ANALOG") (class "Default")
      (node (ref "C2") (pin "1") (pinfunction "1_1") (pintype "unspecified"))
      (node (ref "C35") (pin "1") (pinfunction "1_1") (pintype "unspecified"))
      (node (ref "C36") (pin "2") (pinfunction "2_2") (pintype "unspecified"))
      (node (ref "C7") (pin "2") (pinfunction "2_2") (pintype "unspecified"))
      (node (ref "L2") (pin "1") (pinfunction "1_1") (pintype "unspecified"))
      (node (ref "R11") (pin "1") (pinfunction "1_1") (pintype "input"))
      (node (ref "R6") (pin "2") (pinfunction "2_2") (pintype "input"))
      (node (ref "TP-3v3Analog") (pin "1") (pinfunction "1_1") (pintype "unspecified"))
      (node (ref "U1") (pin "5") (pinfunction "VS_5") (pintype "unspecified"))
      (node (ref "U5") (pin "5") (pinfunction "V+_5") (pintype "unspecified"))
    )
    (net (code "2") (name "3V3_EXT") (class "Default")
      (node (ref "D2") (pin "1") (pinfunction "1_1") (pintype "unspecified"))
      (node (ref "J1") (pin "1") (pinfunction "1_1") (pintype "unspecified"))
      (node (ref "R22") (pin "1") (pinfunction "1_1") (pintype "input"))
    )
    (net (code "3") (name "3V3_LOGIC") (class "Default")
      (node (ref "C14") (pin "2") (pinfunction "2_2") (pintype "unspecified"))
      (node (ref "C15") (pin "2") (pinfunction "2_2") (pintype "unspecified"))
      (node (ref "C17") (pin "1") (pinfunction "1_1") (pintype "unspecified"))
      (node (ref "C18") (pin "2") (pinfunction "2_2") (pintype "unspecified"))
      (node (ref "C37") (pin "2") (pinfunction "2_2") (pintype "unspecified"))
      (node (ref "C38") (pin "2") (pinfunction "2_2") (pintype "unspecified"))
      (node (ref "C5") (pin "1") (pinfunction "1_1") (pintype "unspecified"))
      (node (ref "J8") (pin "2") (pinfunction "2_2") (pintype "unspecified"))
      (node (ref "J9") (pin "2") (pinfunction "2_2") (pintype "unspecified"))
      (node (ref "L1") (pin "1") (pinfunction "1_1") (pintype "input"))
      (node (ref "L2") (pin "2") (pinfunction "2_2") (pintype "unspecified"))
      (node (ref "R16") (pin "1") (pinfunction "1_1") (pintype "input"))
      (node (ref "R21") (pin "2") (pinfunction "2_2") (pintype "input"))
      (node (ref "R22") (pin "2") (pinfunction "2_2") (pintype "input"))
      (node (ref "R23") (pin "2") (pinfunction "2_2") (pintype "input"))
      (node (ref "R24") (pin "2") (pinfunction "2_2") (pintype "input"))
      (node (ref "R25") (pin "2") (pinfunction "2_2") (pintype "input"))
      (node (ref "R3") (pin "2") (pinfunction "2_2") (pintype "input"))
      (node (ref "R35") (pin "1") (pinfunction "1_1") (pintype "unspecified"))
      (node (ref "R37") (pin "1") (pinfunction "1_1") (pintype "input"))
      (node (ref "R38") (pin "2") (pinfunction "2_2") (pintype "input"))
      (node (ref "TP-3v3Logic") (pin "1") (pinfunction "1_1") (pintype "unspecified"))
      (node (ref "U2") (pin "2") (pinfunction "D_2") (pintype "unspecified"))
      (node (ref "U2") (pin "7") (pinfunction "S#D_7") (pintype "unspecified"))
      (node (ref "U2") (pin "8") (pinfunction "VCC_8") (pintype "unspecified"))
      (node (ref "U28") (pin "24") (pinfunction "VCC_24") (pintype "input"))
      (node (ref "U6") (pin "2") (pinfunction "3V3_2") (pintype "unspecified"))
      (node (ref "U7") (pin "5") (pinfunction "VCC_5") (pintype "input"))
    )
    (net (code "4") (name "3V3_MOTOR") (class "Default")
      (node (ref "C21") (pin "2") (pinfunction "2_2") (pintype "unspecified"))
      (node (ref "C22") (pin "2") (pinfunction "2_2") (pintype "unspecified"))
      (node (ref "C25") (pin "2") (pinfunction "2_2") (pintype "unspecified"))
      (node (ref "C26") (pin "2") (pinfunction "2_2") (pintype "unspecified"))
      (node (ref "C29") (pin "2") (pinfunction "2_2") (pintype "unspecified"))
      (node (ref "C30") (pin "2") (pinfunction "2_2") (pintype "unspecified"))
      (node (ref "R2") (pin "2") (pinfunction "2_2") (pintype "unspecified"))
      (node (ref "TP-3v3Motor") (pin "1") (pinfunction "1_1") (pintype "unspecified"))
      (node (ref "U1") (pin "4") (pinfunction "IN-_4") (pintype "unspecified"))
      (node (ref "U10") (pin "12") (pinfunction "VM_12") (pintype "unspecified"))
      (node (ref "U11") (pin "12") (pinfunction "VM_12") (pintype "unspecified"))
      (node (ref "U9") (pin "12") (pinfunction "VM_12") (pintype "unspecified"))
    )
    (net (code "5") (name "3V3_MOTOR_REG") (class "Default")
      (node (ref "C39") (pin "2") (pinfunction "2_2") (pintype "unspecified"))
      (node (ref "C40") (pin "2") (pinfunction "2_2") (pintype "unspecified"))
      (node (ref "C41") (pin "2") (pinfunction "2_2") (pintype "unspecified"))
      (node (ref "R2") (pin "1") (pinfunction "1_1") (pintype "unspecified"))
      (node (ref "U1") (pin "3") (pinfunction "IN+_3") (pintype "unspecified"))
      (node (ref "U26") (pin "5") (pinfunction "VOUT_5") (pintype "unspecified"))
    )
    (net (code "6") (name "ADC_CURRENT") (class "Default")
      (node (ref "C1") (pin "2") (pinfunction "2_2") (pintype "unspecified"))
      (node (ref "R1") (pin "1") (pinfunction "1_1") (pintype "input"))
      (node (ref "TP2") (pin "1") (pinfunction "1_1") (pintype "unspecified"))
      (node (ref "U6") (pin "38") (pinfunction "IO2_38") (pintype "unspecified"))
    )
    (net (code "7") (name "ADC_TACHO") (class "Default")
      (node (ref "R13") (pin "1") (pinfunction "1_1") (pintype "input"))
      (node (ref "U6") (pin "39") (pinfunction "IO1_39") (pintype "unspecified"))
    )
    (net (code "8") (name "AISEN1") (class "Default")
      (node (ref "RSA1") (pin "2") (pinfunction "2_2") (pintype "input"))
      (node (ref "U9") (pin "3") (pinfunction "AISEN_3") (pintype "unspecified"))
    )
    (net (code "9") (name "AISEN3") (class "Default")
      (node (ref "RSA2") (pin "2") (pinfunction "2_2") (pintype "input"))
      (node (ref "U10") (pin "3") (pinfunction "AISEN_3") (pintype "unspecified"))
    )
    (net (code "10") (name "AISEN5") (class "Default")
      (node (ref "RSA3") (pin "2") (pinfunction "2_2") (pintype "input"))
      (node (ref "U11") (pin "3") (pinfunction "AISEN_3") (pintype "unspecified"))
    )
    (net (code "11") (name "ARM_CLK") (class "Default")
      (node (ref "C4") (pin "1") (pinfunction "1_1") (pintype "input"))
      (node (ref "Q1") (pin "3") (pinfunction "D_3") (pintype "unspecified"))
      (node (ref "R5") (pin "2") (pinfunction "2_2") (pintype "input"))
      (node (ref "U2") (pin "1") (pinfunction "CP_1") (pintype "unspecified"))
    )
    (net (code "12") (name "ARM_EDGE_IN") (class "Default")
      (node (ref "C4") (pin "2") (pinfunction "2_2") (pintype "input"))
      (node (ref "R4") (pin "1") (pinfunction "1_1") (pintype "input"))
    )
    (net (code "13") (name "BISEN2") (class "Default")
      (node (ref "RSB1") (pin "2") (pinfunction "2_2") (pintype "input"))
      (node (ref "U9") (pin "6") (pinfunction "BISEN_6") (pintype "unspecified"))
    )
    (net (code "14") (name "BISEN4") (class "Default")
      (node (ref "RSB2") (pin "2") (pinfunction "2_2") (pintype "input"))
      (node (ref "U10") (pin "6") (pinfunction "BISEN_6") (pintype "unspecified"))
    )
    (net (code "15") (name "BISEN6") (class "Default")
      (node (ref "RSB3") (pin "2") (pinfunction "2_2") (pintype "input"))
      (node (ref "U11") (pin "6") (pinfunction "BISEN_6") (pintype "unspecified"))
    )
    (net (code "16") (name "BOOT_N") (class "Default")
      (node (ref "BOOT") (pin "3") (pinfunction "3_3") (pintype "input"))
      (node (ref "BOOT") (pin "4") (pinfunction "4_4") (pintype "input"))
      (node (ref "R25") (pin "1") (pinfunction "1_1") (pintype "input"))
      (node (ref "U6") (pin "27") (pinfunction "IO0_27") (pintype "unspecified"))
    )
    (net (code "17") (name "COMM_TACHO_N") (class "Default")
      (node (ref "R15") (pin "2") (pinfunction "2_2") (pintype "input"))
      (node (ref "R16") (pin "2") (pinfunction "2_2") (pintype "input"))
      (node (ref "TP5") (pin "1") (pinfunction "1_1") (pintype "unspecified"))
      (node (ref "U3") (pin "7") (pinfunction "2OUT_7") (pintype "unspecified"))
      (node (ref "U6") (pin "31") (pinfunction "IO38_31") (pintype "unspecified"))
    )
    (net (code "18") (name "CURRENT_RAW") (class "Default")
      (node (ref "C8") (pin "2") (pinfunction "2_2") (pintype "input"))
      (node (ref "R1") (pin "2") (pinfunction "2_2") (pintype "input"))
      (node (ref "TP1") (pin "1") (pinfunction "1_1") (pintype "unspecified"))
      (node (ref "U1") (pin "1") (pinfunction "OUT_1") (pintype "unspecified"))
      (node (ref "U3") (pin "2") (pinfunction "1IN-_2") (pintype "unspecified"))
    )
    (net (code "19") (name "DECODER_INHIBIT") (class "Default")
      (node (ref "TP-Decoder-Inhibit") (pin "1") (pinfunction "1_1") (pintype "unspecified"))
      (node (ref "U28") (pin "1") (pinfunction "LE_1") (pintype "input"))
      (node (ref "U28") (pin "23") (pinfunction "E_23") (pintype "input"))
      (node (ref "U7") (pin "4") (pinfunction "Y_4") (pintype "input"))
    )
    (net (code "20") (name "DRIVER_N_SLEEP") (class "Default")
      (node (ref "R31") (pin "2") (pinfunction "2_2") (pintype "input"))
      (node (ref "U10") (pin "1") (pinfunction "nSLEEP_1") (pintype "unspecified"))
      (node (ref "U11") (pin "1") (pinfunction "nSLEEP_1") (pintype "unspecified"))
      (node (ref "U2") (pin "5") (pinfunction "Q_5") (pintype "unspecified"))
      (node (ref "U7") (pin "2") (pinfunction "B_2") (pintype "input"))
      (node (ref "U9") (pin "1") (pinfunction "nSLEEP_1") (pintype "unspecified"))
    )
    (net (code "21") (name "ESP_EN") (class "Default")
      (node (ref "C16") (pin "2") (pinfunction "2_2") (pintype "input"))
      (node (ref "R24") (pin "1") (pinfunction "1_1") (pintype "input"))
      (node (ref "RESET") (pin "3") (pinfunction "3_3") (pintype "input"))
      (node (ref "RESET") (pin "4") (pinfunction "4_4") (pintype "input"))
      (node (ref "U6") (pin "3") (pinfunction "EN_3") (pintype "unspecified"))
    )
    (net (code "22") (name "FAULT_N_RAW") (class "Default")
      (node (ref "C3") (pin "1") (pinfunction "1_1") (pintype "unspecified"))
      (node (ref "R3") (pin "1") (pinfunction "1_1") (pintype "input"))
      (node (ref "U10") (pin "8") (pinfunction "nFAULT_8") (pintype "unspecified"))
      (node (ref "U11") (pin "8") (pinfunction "nFAULT_8") (pintype "unspecified"))
      (node (ref "U2") (pin "6") (pinfunction "R#D_6") (pintype "unspecified"))
      (node (ref "U24") (pin "4") (pinfunction "FAULT#_4") (pintype "input"))
      (node (ref "U3") (pin "1") (pinfunction "1OUT_1") (pintype "unspecified"))
      (node (ref "U9") (pin "8") (pinfunction "nFAULT_8") (pintype "unspecified"))
    )
    (net (code "23") (name "FLIM_REF") (class "Default")
      (node (ref "C6") (pin "2") (pinfunction "2_2") (pintype "unspecified"))
      (node (ref "R6") (pin "1") (pinfunction "1_1") (pintype "input"))
      (node (ref "R7") (pin "2") (pinfunction "2_2") (pintype "input"))
      (node (ref "U3") (pin "3") (pinfunction "1IN+_3") (pintype "unspecified"))
    )
    (net (code "24") (name "FWD1") (class "Default")
      (node (ref "U28") (pin "4") (pinfunction "Q7_4") (pintype "input"))
      (node (ref "U9") (pin "16") (pinfunction "AIN1_16") (pintype "unspecified"))
    )
    (net (code "25") (name "FWD2") (class "Default")
      (node (ref "U28") (pin "7") (pinfunction "Q4_7") (pintype "input"))
      (node (ref "U9") (pin "9") (pinfunction "BIN1_9") (pintype "unspecified"))
    )
    (net (code "26") (name "FWD3") (class "Default")
      (node (ref "U10") (pin "16") (pinfunction "AIN1_16") (pintype "unspecified"))
      (node (ref "U28") (pin "13") (pinfunction "Q13_13") (pintype "input"))
    )
    (net (code "27") (name "FWD4") (class "Default")
      (node (ref "U10") (pin "9") (pinfunction "BIN1_9") (pintype "unspecified"))
      (node (ref "U28") (pin "16") (pinfunction "Q14_16") (pintype "input"))
    )
    (net (code "28") (name "FWD5") (class "Default")
      (node (ref "U11") (pin "16") (pinfunction "AIN1_16") (pintype "unspecified"))
      (node (ref "U28") (pin "17") (pinfunction "Q9_17") (pintype "input"))
    )
    (net (code "29") (name "FWD6") (class "Default")
      (node (ref "U11") (pin "9") (pinfunction "BIN1_9") (pintype "unspecified"))
      (node (ref "U28") (pin "20") (pinfunction "Q10_20") (pintype "input"))
    )
    (net (code "30") (name "GND") (class "Default")
      (node (ref "BOOT") (pin "1") (pinfunction "1_1") (pintype "input"))
      (node (ref "BOOT") (pin "2") (pinfunction "2_2") (pintype "input"))
      (node (ref "C1") (pin "1") (pinfunction "1_1") (pintype "unspecified"))
      (node (ref "C11") (pin "2") (pinfunction "2_2") (pintype "unspecified"))
      (node (ref "C14") (pin "1") (pinfunction "1_1") (pintype "unspecified"))
      (node (ref "C15") (pin "1") (pinfunction "1_1") (pintype "unspecified"))
      (node (ref "C16") (pin "1") (pinfunction "1_1") (pintype "input"))
      (node (ref "C17") (pin "2") (pinfunction "2_2") (pintype "unspecified"))
      (node (ref "C18") (pin "1") (pinfunction "1_1") (pintype "unspecified"))
      (node (ref "C2") (pin "2") (pinfunction "2_2") (pintype "unspecified"))
      (node (ref "C21") (pin "1") (pinfunction "1_1") (pintype "unspecified"))
      (node (ref "C22") (pin "1") (pinfunction "1_1") (pintype "unspecified"))
      (node (ref "C25") (pin "1") (pinfunction "1_1") (pintype "unspecified"))
      (node (ref "C26") (pin "1") (pinfunction "1_1") (pintype "unspecified"))
      (node (ref "C29") (pin "1") (pinfunction "1_1") (pintype "unspecified"))
      (node (ref "C3") (pin "2") (pinfunction "2_2") (pintype "unspecified"))
      (node (ref "C30") (pin "1") (pinfunction "1_1") (pintype "unspecified"))
      (node (ref "C31") (pin "1") (pinfunction "1_1") (pintype "input"))
      (node (ref "C32") (pin "1") (pinfunction "1_1") (pintype "unspecified"))
      (node (ref "C33") (pin "1") (pinfunction "1_1") (pintype "unspecified"))
      (node (ref "C34") (pin "1") (pinfunction "1_1") (pintype "unspecified"))
      (node (ref "C35") (pin "2") (pinfunction "2_2") (pintype "unspecified"))
      (node (ref "C36") (pin "1") (pinfunction "1_1") (pintype "unspecified"))
      (node (ref "C37") (pin "1") (pinfunction "1_1") (pintype "unspecified"))
      (node (ref "C38") (pin "1") (pinfunction "1_1") (pintype "unspecified"))
      (node (ref "C39") (pin "1") (pinfunction "1_1") (pintype "unspecified"))
      (node (ref "C40") (pin "1") (pinfunction "1_1") (pintype "unspecified"))
      (node (ref "C41") (pin "1") (pinfunction "1_1") (pintype "unspecified"))
      (node (ref "C5") (pin "2") (pinfunction "2_2") (pintype "unspecified"))
      (node (ref "C6") (pin "1") (pinfunction "1_1") (pintype "unspecified"))
      (node (ref "C7") (pin "1") (pinfunction "1_1") (pintype "unspecified"))
      (node (ref "C9") (pin "1") (pinfunction "1_1") (pintype "unspecified"))
      (node (ref "D1") (pin "2") (pinfunction "2_2") (pintype "unspecified"))
      (node (ref "D2") (pin "2") (pinfunction "2_2") (pintype "unspecified"))
      (node (ref "J1") (pin "3") (pinfunction "3_3") (pintype "unspecified"))
      (node (ref "J8") (pin "1") (pinfunction "1_1") (pintype "unspecified"))
      (node (ref "J9") (pin "1") (pinfunction "1_1") (pintype "unspecified"))
      (node (ref "Q1") (pin "2") (pinfunction "S_2") (pintype "unspecified"))
      (node (ref "R12") (pin "2") (pinfunction "2_2") (pintype "input"))
      (node (ref "R26") (pin "1") (pinfunction "1_1") (pintype "input"))
      (node (ref "R27") (pin "1") (pinfunction "1_1") (pintype "input"))
      (node (ref "R28") (pin "1") (pinfunction "1_1") (pintype "input"))
      (node (ref "R29") (pin "1") (pinfunction "1_1") (pintype "input"))
      (node (ref "R30") (pin "1") (pinfunction "1_1") (pintype "input"))
      (node (ref "R31") (pin "1") (pinfunction "1_1") (pintype "input"))
      (node (ref "R32") (pin "2") (pinfunction "2_2") (pintype "input"))
      (node (ref "R33") (pin "2") (pinfunction "2_2") (pintype "input"))
      (node (ref "R34") (pin "2") (pinfunction "2_2") (pintype "input"))
      (node (ref "R36") (pin "2") (pinfunction "2_2") (pintype "input"))
      (node (ref "R5") (pin "1") (pinfunction "1_1") (pintype "input"))
      (node (ref "R7") (pin "1") (pinfunction "1_1") (pintype "input"))
      (node (ref "RESET") (pin "1") (pinfunction "1_1") (pintype "input"))
      (node (ref "RESET") (pin "2") (pinfunction "2_2") (pintype "input"))
      (node (ref "RSA1") (pin "1") (pinfunction "1_1") (pintype "input"))
      (node (ref "RSA2") (pin "1") (pinfunction "1_1") (pintype "input"))
      (node (ref "RSA3") (pin "1") (pinfunction "1_1") (pintype "input"))
      (node (ref "RSB1") (pin "1") (pinfunction "1_1") (pintype "input"))
      (node (ref "RSB2") (pin "1") (pinfunction "1_1") (pintype "input"))
      (node (ref "RSB3") (pin "1") (pinfunction "1_1") (pintype "input"))
      (node (ref "U1") (pin "2") (pinfunction "GND_2") (pintype "unspecified"))
      (node (ref "U10") (pin "13") (pinfunction "GND_13") (pintype "unspecified"))
      (node (ref "U10") (pin "17") (pinfunction "EP_17") (pintype "unspecified"))
      (node (ref "U11") (pin "13") (pinfunction "GND_13") (pintype "unspecified"))
      (node (ref "U11") (pin "17") (pinfunction "EP_17") (pintype "unspecified"))
      (node (ref "U12") (pin "2") (pinfunction "2_2") (pintype "unspecified"))
      (node (ref "U13") (pin "2") (pinfunction "2_2") (pintype "unspecified"))
      (node (ref "U14") (pin "2") (pinfunction "2_2") (pintype "unspecified"))
      (node (ref "U15") (pin "2") (pinfunction "2_2") (pintype "unspecified"))
      (node (ref "U16") (pin "2") (pinfunction "2_2") (pintype "unspecified"))
      (node (ref "U17") (pin "2") (pinfunction "2_2") (pintype "unspecified"))
      (node (ref "U18") (pin "2") (pinfunction "2_2") (pintype "unspecified"))
      (node (ref "U19") (pin "2") (pinfunction "2_2") (pintype "unspecified"))
      (node (ref "U2") (pin "4") (pinfunction "GND_4") (pintype "unspecified"))
      (node (ref "U20") (pin "2") (pinfunction "2_2") (pintype "unspecified"))
      (node (ref "U21") (pin "2") (pinfunction "2_2") (pintype "unspecified"))
      (node (ref "U22") (pin "2") (pinfunction "2_2") (pintype "unspecified"))
      (node (ref "U23") (pin "2") (pinfunction "2_2") (pintype "unspecified"))
      (node (ref "U24") (pin "2") (pinfunction "GND_2") (pintype "input"))
      (node (ref "U25") (pin "2") (pinfunction "GND_2") (pintype "unspecified"))
      (node (ref "U26") (pin "2") (pinfunction "GND_2") (pintype "unspecified"))
      (node (ref "U27") (pin "2") (pinfunction "2_2") (pintype "input"))
      (node (ref "U28") (pin "12") (pinfunction "GND_12") (pintype "input"))
      (node (ref "U3") (pin "4") (pinfunction "GND_4") (pintype "unspecified"))
      (node (ref "U5") (pin "2") (pinfunction "V-_2") (pintype "unspecified"))
      (node (ref "U6") (pin "1") (pinfunction "GND_1") (pintype "unspecified"))
      (node (ref "U6") (pin "40") (pinfunction "GND_40") (pintype "unspecified"))
      (node (ref "U6") (pin "41") (pinfunction "GND_41") (pintype "unspecified"))
      (node (ref "U7") (pin "3") (pinfunction "GND_3") (pintype "input"))
      (node (ref "U9") (pin "13") (pinfunction "GND_13") (pintype "unspecified"))
      (node (ref "U9") (pin "17") (pinfunction "EP_17") (pintype "unspecified"))
      (node (ref "USBC1") (pin "1") (pinfunction "EH_1") (pintype "unspecified"))
      (node (ref "USBC1") (pin "2") (pinfunction "EH_2") (pintype "unspecified"))
      (node (ref "USBC1") (pin "3") (pinfunction "EH_3") (pintype "unspecified"))
      (node (ref "USBC1") (pin "4") (pinfunction "EH_4") (pintype "unspecified"))
      (node (ref "USBC1") (pin "A1B12") (pinfunction "GND_A1B12") (pintype "unspecified"))
      (node (ref "USBC1") (pin "B1A12") (pinfunction "GND_B1A12") (pintype "unspecified"))
    )
    (net (code "31") (name "I2C_SCL") (class "Default")
      (node (ref "J8") (pin "3") (pinfunction "3_3") (pintype "unspecified"))
      (node (ref "R37") (pin "2") (pinfunction "2_2") (pintype "input"))
      (node (ref "U6") (pin "24") (pinfunction "IO47_24") (pintype "unspecified"))
    )
    (net (code "32") (name "I2C_SDA") (class "Default")
      (node (ref "J8") (pin "4") (pinfunction "4_4") (pintype "unspecified"))
      (node (ref "R38") (pin "1") (pinfunction "1_1") (pintype "input"))
      (node (ref "U6") (pin "23") (pinfunction "IO21_23") (pintype "unspecified"))
    )
    (net (code "33") (name "LATCH_ARM") (class "Default")
      (node (ref "R4") (pin "2") (pinfunction "2_2") (pintype "input"))
      (node (ref "U6") (pin "10") (pinfunction "IO17_10") (pintype "unspecified"))
    )
    (net (code "34") (name "LATCH_STATE") (class "Default")
      (node (ref "U2") (pin "3") (pinfunction "Q#_3") (pintype "unspecified"))
      (node (ref "U6") (pin "9") (pinfunction "IO16_9") (pintype "unspecified"))
    )
    (net (code "35") (name "LOGIC_FB") (class "Default")
      (node (ref "R35") (pin "2") (pinfunction "2_2") (pintype "unspecified"))
      (node (ref "R36") (pin "1") (pinfunction "1_1") (pintype "input"))
      (node (ref "U25") (pin "5") (pinfunction "FB_5") (pintype "unspecified"))
    )
    (net (code "36") (name "LOGIC_SW") (class "Default")
      (node (ref "L1") (pin "2") (pinfunction "2_2") (pintype "input"))
      (node (ref "U25") (pin "3") (pinfunction "LX_3") (pintype "unspecified"))
    )
    (net (code "37") (name "MOTOR_1A") (class "Default")
      (node (ref "L3") (pin "1") (pinfunction "1_1") (pintype "unspecified"))
      (node (ref "U9") (pin "2") (pinfunction "AOUT1_2") (pintype "unspecified"))
    )
    (net (code "38") (name "MOTOR_1A_J") (class "Default")
      (node (ref "J2") (pin "1") (pinfunction "1_1") (pintype "unspecified"))
      (node (ref "L3") (pin "2") (pinfunction "2_2") (pintype "unspecified"))
      (node (ref "U12") (pin "1") (pinfunction "1_1") (pintype "unspecified"))
    )
    (net (code "39") (name "MOTOR_1B") (class "Default")
      (node (ref "L4") (pin "1") (pinfunction "1_1") (pintype "unspecified"))
      (node (ref "U9") (pin "4") (pinfunction "AOUT2_4") (pintype "unspecified"))
    )
    (net (code "40") (name "MOTOR_1B_J") (class "Default")
      (node (ref "J2") (pin "3") (pinfunction "3_3") (pintype "unspecified"))
      (node (ref "L4") (pin "2") (pinfunction "2_2") (pintype "unspecified"))
      (node (ref "U13") (pin "1") (pinfunction "1_1") (pintype "unspecified"))
    )
    (net (code "41") (name "MOTOR_2A") (class "Default")
      (node (ref "L5") (pin "1") (pinfunction "1_1") (pintype "unspecified"))
      (node (ref "U9") (pin "7") (pinfunction "BOUT1_7") (pintype "unspecified"))
    )
    (net (code "42") (name "MOTOR_2A_J") (class "Default")
      (node (ref "J3") (pin "1") (pinfunction "1_1") (pintype "unspecified"))
      (node (ref "L5") (pin "2") (pinfunction "2_2") (pintype "unspecified"))
      (node (ref "U14") (pin "1") (pinfunction "1_1") (pintype "unspecified"))
    )
    (net (code "43") (name "MOTOR_2B") (class "Default")
      (node (ref "L6") (pin "1") (pinfunction "1_1") (pintype "unspecified"))
      (node (ref "U9") (pin "5") (pinfunction "BOUT2_5") (pintype "unspecified"))
    )
    (net (code "44") (name "MOTOR_2B_J") (class "Default")
      (node (ref "J3") (pin "3") (pinfunction "3_3") (pintype "unspecified"))
      (node (ref "L6") (pin "2") (pinfunction "2_2") (pintype "unspecified"))
      (node (ref "U15") (pin "1") (pinfunction "1_1") (pintype "unspecified"))
    )
    (net (code "45") (name "MOTOR_3A") (class "Default")
      (node (ref "L7") (pin "1") (pinfunction "1_1") (pintype "unspecified"))
      (node (ref "U10") (pin "2") (pinfunction "AOUT1_2") (pintype "unspecified"))
    )
    (net (code "46") (name "MOTOR_3A_J") (class "Default")
      (node (ref "J4") (pin "1") (pinfunction "1_1") (pintype "unspecified"))
      (node (ref "L7") (pin "2") (pinfunction "2_2") (pintype "unspecified"))
      (node (ref "U16") (pin "1") (pinfunction "1_1") (pintype "unspecified"))
    )
    (net (code "47") (name "MOTOR_3B") (class "Default")
      (node (ref "L8") (pin "1") (pinfunction "1_1") (pintype "unspecified"))
      (node (ref "U10") (pin "4") (pinfunction "AOUT2_4") (pintype "unspecified"))
    )
    (net (code "48") (name "MOTOR_3B_J") (class "Default")
      (node (ref "J4") (pin "3") (pinfunction "3_3") (pintype "unspecified"))
      (node (ref "L8") (pin "2") (pinfunction "2_2") (pintype "unspecified"))
      (node (ref "U17") (pin "1") (pinfunction "1_1") (pintype "unspecified"))
    )
    (net (code "49") (name "MOTOR_4A") (class "Default")
      (node (ref "L9") (pin "1") (pinfunction "1_1") (pintype "unspecified"))
      (node (ref "U10") (pin "7") (pinfunction "BOUT1_7") (pintype "unspecified"))
    )
    (net (code "50") (name "MOTOR_4A_J") (class "Default")
      (node (ref "J5") (pin "1") (pinfunction "1_1") (pintype "unspecified"))
      (node (ref "L9") (pin "2") (pinfunction "2_2") (pintype "unspecified"))
      (node (ref "U18") (pin "1") (pinfunction "1_1") (pintype "unspecified"))
    )
    (net (code "51") (name "MOTOR_4B") (class "Default")
      (node (ref "L10") (pin "1") (pinfunction "1_1") (pintype "unspecified"))
      (node (ref "U10") (pin "5") (pinfunction "BOUT2_5") (pintype "unspecified"))
    )
    (net (code "52") (name "MOTOR_4B_J") (class "Default")
      (node (ref "J5") (pin "3") (pinfunction "3_3") (pintype "unspecified"))
      (node (ref "L10") (pin "2") (pinfunction "2_2") (pintype "unspecified"))
      (node (ref "U19") (pin "1") (pinfunction "1_1") (pintype "unspecified"))
    )
    (net (code "53") (name "MOTOR_5A") (class "Default")
      (node (ref "L11") (pin "1") (pinfunction "1_1") (pintype "unspecified"))
      (node (ref "U11") (pin "2") (pinfunction "AOUT1_2") (pintype "unspecified"))
    )
    (net (code "54") (name "MOTOR_5A_J") (class "Default")
      (node (ref "J6") (pin "1") (pinfunction "1_1") (pintype "unspecified"))
      (node (ref "L11") (pin "2") (pinfunction "2_2") (pintype "unspecified"))
      (node (ref "U20") (pin "1") (pinfunction "1_1") (pintype "unspecified"))
    )
    (net (code "55") (name "MOTOR_5B") (class "Default")
      (node (ref "L12") (pin "1") (pinfunction "1_1") (pintype "unspecified"))
      (node (ref "U11") (pin "4") (pinfunction "AOUT2_4") (pintype "unspecified"))
    )
    (net (code "56") (name "MOTOR_5B_J") (class "Default")
      (node (ref "J6") (pin "3") (pinfunction "3_3") (pintype "unspecified"))
      (node (ref "L12") (pin "2") (pinfunction "2_2") (pintype "unspecified"))
      (node (ref "U21") (pin "1") (pinfunction "1_1") (pintype "unspecified"))
    )
    (net (code "57") (name "MOTOR_6A") (class "Default")
      (node (ref "L13") (pin "1") (pinfunction "1_1") (pintype "unspecified"))
      (node (ref "U11") (pin "7") (pinfunction "BOUT1_7") (pintype "unspecified"))
    )
    (net (code "58") (name "MOTOR_6A_J") (class "Default")
      (node (ref "J7") (pin "1") (pinfunction "1_1") (pintype "unspecified"))
      (node (ref "L13") (pin "2") (pinfunction "2_2") (pintype "unspecified"))
      (node (ref "U22") (pin "1") (pinfunction "1_1") (pintype "unspecified"))
    )
    (net (code "59") (name "MOTOR_6B") (class "Default")
      (node (ref "L14") (pin "1") (pinfunction "1_1") (pintype "unspecified"))
      (node (ref "U11") (pin "5") (pinfunction "BOUT2_5") (pintype "unspecified"))
    )
    (net (code "60") (name "MOTOR_6B_J") (class "Default")
      (node (ref "J7") (pin "3") (pinfunction "3_3") (pintype "unspecified"))
      (node (ref "L14") (pin "2") (pinfunction "2_2") (pintype "unspecified"))
      (node (ref "U23") (pin "1") (pinfunction "1_1") (pintype "unspecified"))
    )
    (net (code "61") (name "MOTOR_ADDR0") (class "Default")
      (node (ref "R26") (pin "2") (pinfunction "2_2") (pintype "input"))
      (node (ref "U28") (pin "2") (pinfunction "A0_2") (pintype "input"))
      (node (ref "U6") (pin "20") (pinfunction "IO12_20") (pintype "unspecified"))
    )
    (net (code "62") (name "MOTOR_ADDR1") (class "Default")
      (node (ref "R27") (pin "2") (pinfunction "2_2") (pintype "input"))
      (node (ref "U28") (pin "3") (pinfunction "A1_3") (pintype "input"))
      (node (ref "U6") (pin "19") (pinfunction "IO11_19") (pintype "unspecified"))
    )
    (net (code "63") (name "MOTOR_ADDR2") (class "Default")
      (node (ref "R28") (pin "2") (pinfunction "2_2") (pintype "input"))
      (node (ref "U28") (pin "21") (pinfunction "A2_21") (pintype "input"))
      (node (ref "U6") (pin "22") (pinfunction "IO14_22") (pintype "unspecified"))
    )
    (net (code "64") (name "MOTOR_ADDR3") (class "Default")
      (node (ref "R29") (pin "2") (pinfunction "2_2") (pintype "input"))
      (node (ref "U28") (pin "22") (pinfunction "A3_22") (pintype "input"))
      (node (ref "U6") (pin "21") (pinfunction "IO13_21") (pintype "unspecified"))
    )
    (net (code "65") (name "MOTOR_ENABLE") (class "Default")
      (node (ref "Q1") (pin "1") (pinfunction "G_1") (pintype "unspecified"))
      (node (ref "R30") (pin "2") (pinfunction "2_2") (pintype "input"))
      (node (ref "U6") (pin "11") (pinfunction "IO18_11") (pintype "unspecified"))
      (node (ref "U7") (pin "1") (pinfunction "A_1") (pintype "input"))
    )
    (net (code "66") (name "ONEWIRE_BUS") (class "Default")
      (node (ref "D1") (pin "1") (pinfunction "1_1") (pintype "unspecified"))
      (node (ref "J1") (pin "2") (pinfunction "2_2") (pintype "unspecified"))
      (node (ref "R20") (pin "1") (pinfunction "1_1") (pintype "input"))
      (node (ref "R21") (pin "1") (pinfunction "1_1") (pintype "input"))
    )
    (net (code "67") (name "ONEWIRE_MCU") (class "Default")
      (node (ref "R20") (pin "2") (pinfunction "2_2") (pintype "input"))
      (node (ref "U6") (pin "12") (pinfunction "IO8_12") (pintype "unspecified"))
    )
    (net (code "68") (name "REV1") (class "Default")
      (node (ref "U28") (pin "5") (pinfunction "Q6_5") (pintype "input"))
      (node (ref "U9") (pin "15") (pinfunction "AIN2_15") (pintype "unspecified"))
    )
    (net (code "69") (name "REV2") (class "Default")
      (node (ref "U28") (pin "6") (pinfunction "Q5_6") (pintype "input"))
      (node (ref "U9") (pin "10") (pinfunction "BIN2_10") (pintype "unspecified"))
    )
    (net (code "70") (name "REV3") (class "Default")
      (node (ref "U10") (pin "15") (pinfunction "AIN2_15") (pintype "unspecified"))
      (node (ref "U28") (pin "14") (pinfunction "Q12_14") (pintype "input"))
    )
    (net (code "71") (name "REV4") (class "Default")
      (node (ref "U10") (pin "10") (pinfunction "BIN2_10") (pintype "unspecified"))
      (node (ref "U28") (pin "15") (pinfunction "Q15_15") (pintype "input"))
    )
    (net (code "72") (name "REV5") (class "Default")
      (node (ref "U11") (pin "15") (pinfunction "AIN2_15") (pintype "unspecified"))
      (node (ref "U28") (pin "18") (pinfunction "Q8_18") (pintype "input"))
    )
    (net (code "73") (name "REV6") (class "Default")
      (node (ref "U11") (pin "10") (pinfunction "BIN2_10") (pintype "unspecified"))
      (node (ref "U28") (pin "19") (pinfunction "Q11_19") (pintype "input"))
    )
    (net (code "74") (name "STATUS_LED_A") (class "Default")
      (node (ref "D3") (pin "1") (pinfunction "A_1") (pintype "unspecified"))
      (node (ref "R23") (pin "1") (pinfunction "1_1") (pintype "input"))
    )
    (net (code "75") (name "STATUS_LED_N") (class "Default")
      (node (ref "D3") (pin "2") (pinfunction "K_2") (pintype "unspecified"))
      (node (ref "U6") (pin "4") (pinfunction "IO4_4") (pintype "unspecified"))
    )
    (net (code "76") (name "TACHO_AC") (class "Default")
      (node (ref "C8") (pin "1") (pinfunction "1_1") (pintype "input"))
      (node (ref "R9") (pin "1") (pinfunction "1_1") (pintype "input"))
      (node (ref "U5") (pin "3") (pinfunction "IN+_3") (pintype "unspecified"))
    )
    (net (code "77") (name "TACHO_AMP") (class "Default")
      (node (ref "C10") (pin "2") (pinfunction "2_2") (pintype "input"))
      (node (ref "R10") (pin "1") (pinfunction "1_1") (pintype "input"))
      (node (ref "R13") (pin "2") (pinfunction "2_2") (pintype "input"))
      (node (ref "R14") (pin "1") (pinfunction "1_1") (pintype "input"))
      (node (ref "TP4") (pin "1") (pinfunction "1_1") (pintype "unspecified"))
      (node (ref "U5") (pin "1") (pinfunction "OUT_1") (pintype "unspecified"))
    )
    (net (code "78") (name "TACHO_CMP") (class "Default")
      (node (ref "R14") (pin "2") (pinfunction "2_2") (pintype "input"))
      (node (ref "R15") (pin "1") (pinfunction "1_1") (pintype "input"))
      (node (ref "U3") (pin "5") (pinfunction "2IN+_5") (pintype "unspecified"))
    )
    (net (code "79") (name "TACHO_FB") (class "Default")
      (node (ref "C10") (pin "1") (pinfunction "1_1") (pintype "input"))
      (node (ref "R10") (pin "2") (pinfunction "2_2") (pintype "input"))
      (node (ref "R8") (pin "2") (pinfunction "2_2") (pintype "input"))
      (node (ref "U5") (pin "4") (pinfunction "IN-_4") (pintype "unspecified"))
    )
    (net (code "80") (name "TACHO_REF") (class "Default")
      (node (ref "C9") (pin "2") (pinfunction "2_2") (pintype "unspecified"))
      (node (ref "R11") (pin "2") (pinfunction "2_2") (pintype "input"))
      (node (ref "R12") (pin "1") (pinfunction "1_1") (pintype "input"))
      (node (ref "R8") (pin "1") (pinfunction "1_1") (pintype "input"))
      (node (ref "R9") (pin "2") (pinfunction "2_2") (pintype "input"))
      (node (ref "U3") (pin "6") (pinfunction "2IN-_6") (pintype "unspecified"))
    )
    (net (code "81") (name "UART_RX") (class "Default")
      (node (ref "R40") (pin "1") (pinfunction "1_1") (pintype "input"))
      (node (ref "U6") (pin "36") (pinfunction "RXD0_36") (pintype "unspecified"))
    )
    (net (code "82") (name "UART_RX_DBG") (class "Default")
      (node (ref "J9") (pin "4") (pinfunction "4_4") (pintype "unspecified"))
      (node (ref "R40") (pin "2") (pinfunction "2_2") (pintype "input"))
    )
    (net (code "83") (name "UART_TX") (class "Default")
      (node (ref "R39") (pin "1") (pinfunction "1_1") (pintype "input"))
      (node (ref "U6") (pin "37") (pinfunction "TXD0_37") (pintype "unspecified"))
    )
    (net (code "84") (name "UART_TX_DBG") (class "Default")
      (node (ref "J9") (pin "3") (pinfunction "3_3") (pintype "unspecified"))
      (node (ref "R39") (pin "2") (pinfunction "2_2") (pintype "input"))
    )
    (net (code "85") (name "USB_CC1") (class "Default")
      (node (ref "R33") (pin "1") (pinfunction "1_1") (pintype "input"))
      (node (ref "USBC1") (pin "A5") (pinfunction "CC1_A5") (pintype "unspecified"))
    )
    (net (code "86") (name "USB_CC2") (class "Default")
      (node (ref "R32") (pin "1") (pinfunction "1_1") (pintype "input"))
      (node (ref "USBC1") (pin "B5") (pinfunction "CC2_B5") (pintype "unspecified"))
    )
    (net (code "87") (name "USB_DM") (class "Default")
      (node (ref "U27") (pin "6") (pinfunction "6_6") (pintype "input"))
      (node (ref "U6") (pin "13") (pinfunction "IO19_13") (pintype "unspecified"))
    )
    (net (code "88") (name "USB_DN_IN") (class "Default")
      (node (ref "U27") (pin "1") (pinfunction "1_1") (pintype "input"))
      (node (ref "USBC1") (pin "A7") (pinfunction "DN1_A7") (pintype "unspecified"))
      (node (ref "USBC1") (pin "B7") (pinfunction "DN2_B7") (pintype "unspecified"))
    )
    (net (code "89") (name "USB_DP") (class "Default")
      (node (ref "U27") (pin "4") (pinfunction "4_4") (pintype "input"))
      (node (ref "U6") (pin "14") (pinfunction "IO20_14") (pintype "unspecified"))
    )
    (net (code "90") (name "USB_DP_IN") (class "Default")
      (node (ref "U27") (pin "3") (pinfunction "3_3") (pintype "input"))
      (node (ref "USBC1") (pin "A6") (pinfunction "DP1_A6") (pintype "unspecified"))
      (node (ref "USBC1") (pin "B6") (pinfunction "DP2_B6") (pintype "unspecified"))
    )
    (net (code "91") (name "USB_ILIM") (class "Default")
      (node (ref "R34") (pin "1") (pinfunction "1_1") (pintype "input"))
      (node (ref "U24") (pin "5") (pinfunction "ILIM_5") (pintype "input"))
    )
    (net (code "92") (name "VBUS_PROTECTED") (class "Default")
      (node (ref "C11") (pin "1") (pinfunction "1_1") (pintype "unspecified"))
      (node (ref "C32") (pin "2") (pinfunction "2_2") (pintype "unspecified"))
      (node (ref "C33") (pin "2") (pinfunction "2_2") (pintype "unspecified"))
      (node (ref "C34") (pin "2") (pinfunction "2_2") (pintype "unspecified"))
      (node (ref "TP-VBUS_PROTECTED") (pin "1") (pinfunction "1_1") (pintype "unspecified"))
      (node (ref "U24") (pin "6") (pinfunction "OUT_6") (pintype "input"))
      (node (ref "U25") (pin "1") (pinfunction "EN_1") (pintype "unspecified"))
      (node (ref "U25") (pin "4") (pinfunction "IN_4") (pintype "unspecified"))
      (node (ref "U26") (pin "1") (pinfunction "VIN_1") (pintype "unspecified"))
      (node (ref "U26") (pin "3") (pinfunction "EN_3") (pintype "unspecified"))
      (node (ref "U3") (pin "8") (pinfunction "VCC+_8") (pintype "unspecified"))
    )
    (net (code "93") (name "VBUS_RAW") (class "Default")
      (node (ref "C31") (pin "2") (pinfunction "2_2") (pintype "input"))
      (node (ref "TP-VBUS_RAW") (pin "1") (pinfunction "1_1") (pintype "unspecified"))
      (node (ref "U24") (pin "1") (pinfunction "IN_1") (pintype "input"))
      (node (ref "U24") (pin "3") (pinfunction "EN_3") (pintype "input"))
      (node (ref "U27") (pin "5") (pinfunction "5_5") (pintype "input"))
      (node (ref "USBC1") (pin "A4B9") (pinfunction "VBUS_A4B9") (pintype "unspecified"))
      (node (ref "USBC1") (pin "B4A9") (pinfunction "VBUS_B4A9") (pintype "unspecified"))
    )
    (net (code "94") (name "unconnected-(J2-Pad2)") (class "Default")
      (node (ref "J2") (pin "2") (pinfunction "2_2") (pintype "unspecified+no_connect"))
    )
    (net (code "95") (name "unconnected-(J2-Pad4)") (class "Default")
      (node (ref "J2") (pin "4") (pinfunction "4_4") (pintype "unspecified+no_connect"))
    )
    (net (code "96") (name "unconnected-(J3-Pad2)") (class "Default")
      (node (ref "J3") (pin "2") (pinfunction "2_2") (pintype "unspecified+no_connect"))
    )
    (net (code "97") (name "unconnected-(J3-Pad4)") (class "Default")
      (node (ref "J3") (pin "4") (pinfunction "4_4") (pintype "unspecified+no_connect"))
    )
    (net (code "98") (name "unconnected-(J4-Pad2)") (class "Default")
      (node (ref "J4") (pin "2") (pinfunction "2_2") (pintype "unspecified+no_connect"))
    )
    (net (code "99") (name "unconnected-(J4-Pad4)") (class "Default")
      (node (ref "J4") (pin "4") (pinfunction "4_4") (pintype "unspecified+no_connect"))
    )
    (net (code "100") (name "unconnected-(J5-Pad2)") (class "Default")
      (node (ref "J5") (pin "2") (pinfunction "2_2") (pintype "unspecified+no_connect"))
    )
    (net (code "101") (name "unconnected-(J5-Pad4)") (class "Default")
      (node (ref "J5") (pin "4") (pinfunction "4_4") (pintype "unspecified+no_connect"))
    )
    (net (code "102") (name "unconnected-(J6-Pad2)") (class "Default")
      (node (ref "J6") (pin "2") (pinfunction "2_2") (pintype "unspecified+no_connect"))
    )
    (net (code "103") (name "unconnected-(J6-Pad4)") (class "Default")
      (node (ref "J6") (pin "4") (pinfunction "4_4") (pintype "unspecified+no_connect"))
    )
    (net (code "104") (name "unconnected-(J7-Pad2)") (class "Default")
      (node (ref "J7") (pin "2") (pinfunction "2_2") (pintype "unspecified+no_connect"))
    )
    (net (code "105") (name "unconnected-(J7-Pad4)") (class "Default")
      (node (ref "J7") (pin "4") (pinfunction "4_4") (pintype "unspecified+no_connect"))
    )
    (net (code "106") (name "unconnected-(U6-IO3-Pad15)") (class "Default")
      (node (ref "U6") (pin "15") (pinfunction "IO3_15") (pintype "unspecified+no_connect"))
    )
    (net (code "107") (name "unconnected-(U6-IO5-Pad5)") (class "Default")
      (node (ref "U6") (pin "5") (pinfunction "IO5_5") (pintype "unspecified+no_connect"))
    )
    (net (code "108") (name "unconnected-(U6-IO6-Pad6)") (class "Default")
      (node (ref "U6") (pin "6") (pinfunction "IO6_6") (pintype "unspecified+no_connect"))
    )
    (net (code "109") (name "unconnected-(U6-IO7-Pad7)") (class "Default")
      (node (ref "U6") (pin "7") (pinfunction "IO7_7") (pintype "unspecified+no_connect"))
    )
    (net (code "110") (name "unconnected-(U6-IO9-Pad17)") (class "Default")
      (node (ref "U6") (pin "17") (pinfunction "IO9_17") (pintype "unspecified+no_connect"))
    )
    (net (code "111") (name "unconnected-(U6-IO10-Pad18)") (class "Default")
      (node (ref "U6") (pin "18") (pinfunction "IO10_18") (pintype "unspecified+no_connect"))
    )
    (net (code "112") (name "unconnected-(U6-IO15-Pad8)") (class "Default")
      (node (ref "U6") (pin "8") (pinfunction "IO15_8") (pintype "unspecified+no_connect"))
    )
    (net (code "113") (name "unconnected-(U6-IO35-Pad28)") (class "Default")
      (node (ref "U6") (pin "28") (pinfunction "IO35_28") (pintype "unspecified+no_connect"))
    )
    (net (code "114") (name "unconnected-(U6-IO36-Pad29)") (class "Default")
      (node (ref "U6") (pin "29") (pinfunction "IO36_29") (pintype "unspecified+no_connect"))
    )
    (net (code "115") (name "unconnected-(U6-IO37-Pad30)") (class "Default")
      (node (ref "U6") (pin "30") (pinfunction "IO37_30") (pintype "unspecified+no_connect"))
    )
    (net (code "116") (name "unconnected-(U6-IO39-Pad32)") (class "Default")
      (node (ref "U6") (pin "32") (pinfunction "IO39_32") (pintype "unspecified+no_connect"))
    )
    (net (code "117") (name "unconnected-(U6-IO40-Pad33)") (class "Default")
      (node (ref "U6") (pin "33") (pinfunction "IO40_33") (pintype "unspecified+no_connect"))
    )
    (net (code "118") (name "unconnected-(U6-IO41-Pad34)") (class "Default")
      (node (ref "U6") (pin "34") (pinfunction "IO41_34") (pintype "unspecified+no_connect"))
    )
    (net (code "119") (name "unconnected-(U6-IO42-Pad35)") (class "Default")
      (node (ref "U6") (pin "35") (pinfunction "IO42_35") (pintype "unspecified+no_connect"))
    )
    (net (code "120") (name "unconnected-(U6-IO45-Pad26)") (class "Default")
      (node (ref "U6") (pin "26") (pinfunction "IO45_26") (pintype "unspecified+no_connect"))
    )
    (net (code "121") (name "unconnected-(U6-IO46-Pad16)") (class "Default")
      (node (ref "U6") (pin "16") (pinfunction "IO46_16") (pintype "unspecified+no_connect"))
    )
    (net (code "122") (name "unconnected-(U6-IO48-Pad25)") (class "Default")
      (node (ref "U6") (pin "25") (pinfunction "IO48_25") (pintype "unspecified+no_connect"))
    )
    (net (code "123") (name "unconnected-(U9-NC-Pad11)") (class "Default")
      (node (ref "U9") (pin "11") (pinfunction "NC_11") (pintype "unspecified+no_connect"))
    )
    (net (code "124") (name "unconnected-(U9-NC-Pad14)") (class "Default")
      (node (ref "U9") (pin "14") (pinfunction "NC_14") (pintype "unspecified+no_connect"))
    )
    (net (code "125") (name "unconnected-(U10-NC-Pad11)") (class "Default")
      (node (ref "U10") (pin "11") (pinfunction "NC_11") (pintype "unspecified+no_connect"))
    )
    (net (code "126") (name "unconnected-(U10-NC-Pad14)") (class "Default")
      (node (ref "U10") (pin "14") (pinfunction "NC_14") (pintype "unspecified+no_connect"))
    )
    (net (code "127") (name "unconnected-(U11-NC-Pad11)") (class "Default")
      (node (ref "U11") (pin "11") (pinfunction "NC_11") (pintype "unspecified+no_connect"))
    )
    (net (code "128") (name "unconnected-(U11-NC-Pad14)") (class "Default")
      (node (ref "U11") (pin "14") (pinfunction "NC_14") (pintype "unspecified+no_connect"))
    )
    (net (code "129") (name "unconnected-(U26-NC-Pad4)") (class "Default")
      (node (ref "U26") (pin "4") (pinfunction "NC_4") (pintype "unspecified+no_connect"))
    )
    (net (code "130") (name "unconnected-(U28-Q0-Pad11)") (class "Default")
      (node (ref "U28") (pin "11") (pinfunction "Q0_11") (pintype "input+no_connect"))
    )
    (net (code "131") (name "unconnected-(U28-Q1-Pad9)") (class "Default")
      (node (ref "U28") (pin "9") (pinfunction "Q1_9") (pintype "input+no_connect"))
    )
    (net (code "132") (name "unconnected-(U28-Q2-Pad10)") (class "Default")
      (node (ref "U28") (pin "10") (pinfunction "Q2_10") (pintype "input+no_connect"))
    )
    (net (code "133") (name "unconnected-(U28-Q3-Pad8)") (class "Default")
      (node (ref "U28") (pin "8") (pinfunction "Q3_8") (pintype "input+no_connect"))
    )
    (net (code "134") (name "unconnected-(USBC1-SBU1-PadA8)") (class "Default")
      (node (ref "USBC1") (pin "A8") (pinfunction "SBU1_A8") (pintype "unspecified+no_connect"))
    )
    (net (code "135") (name "unconnected-(USBC1-SBU2-PadB8)") (class "Default")
      (node (ref "USBC1") (pin "B8") (pinfunction "SBU2_B8") (pintype "unspecified+no_connect"))
    )
  )
)
